# Sensormain_of_Tatebayashi.net
KiCad netlist of a schematic drawn in EAGLE
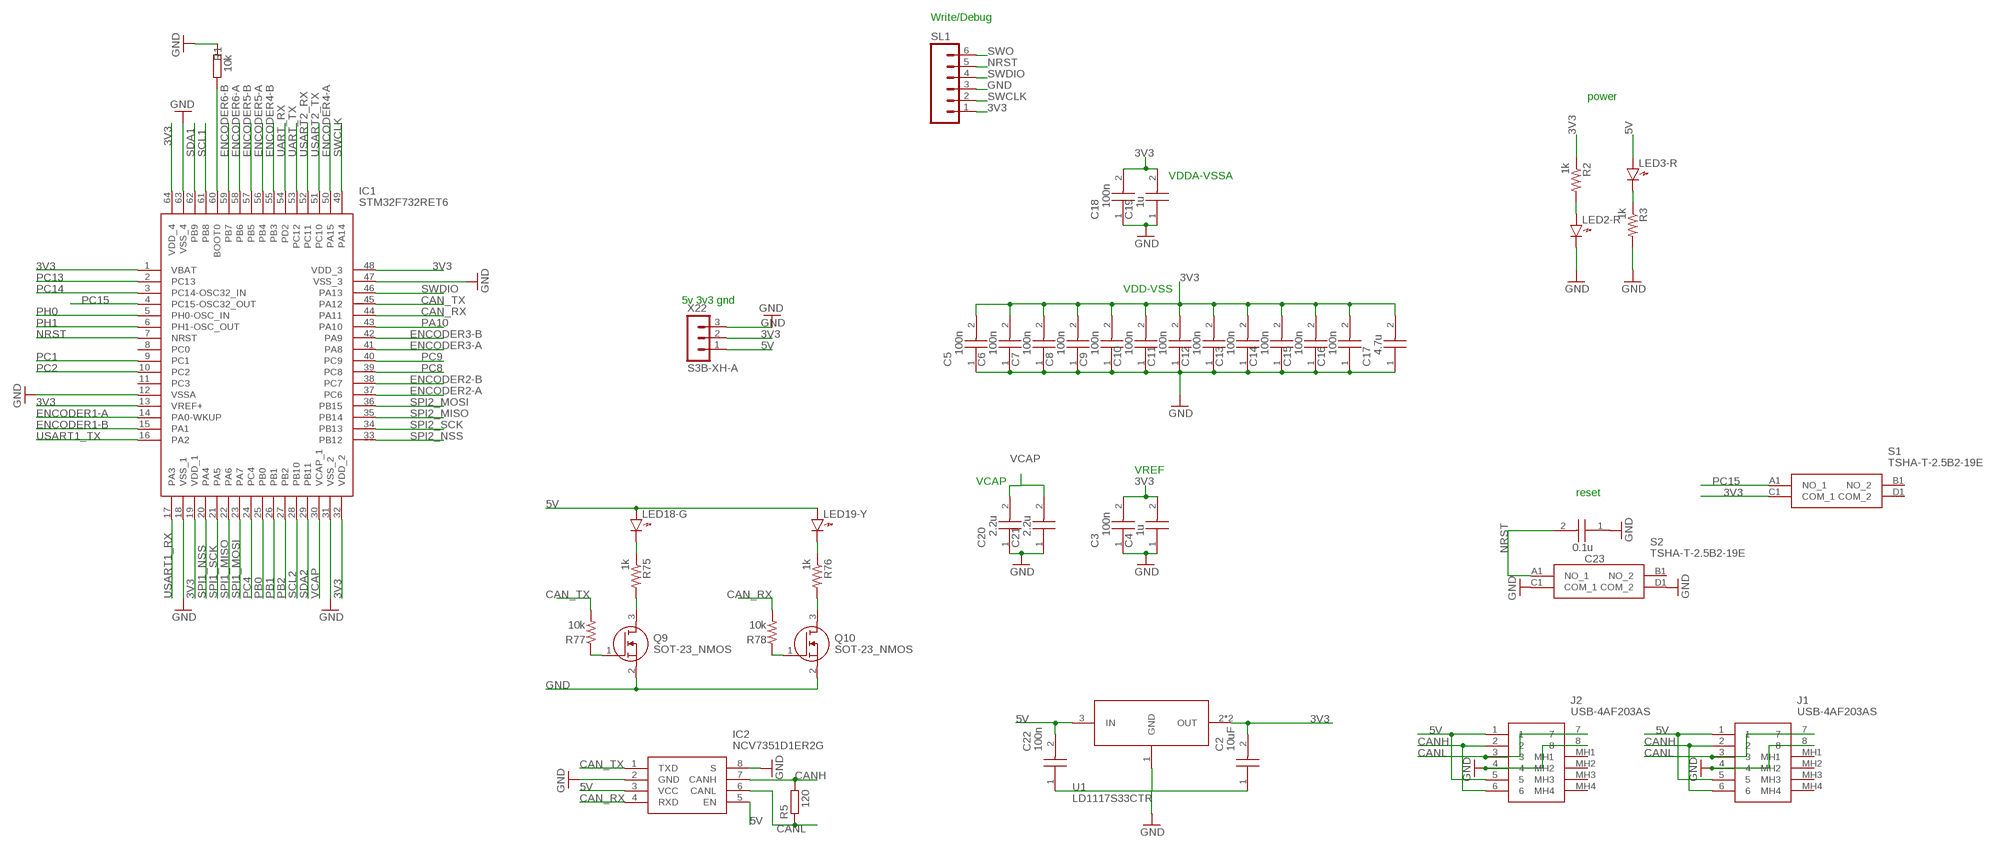
[diagram p0: schematic, sheet 1]
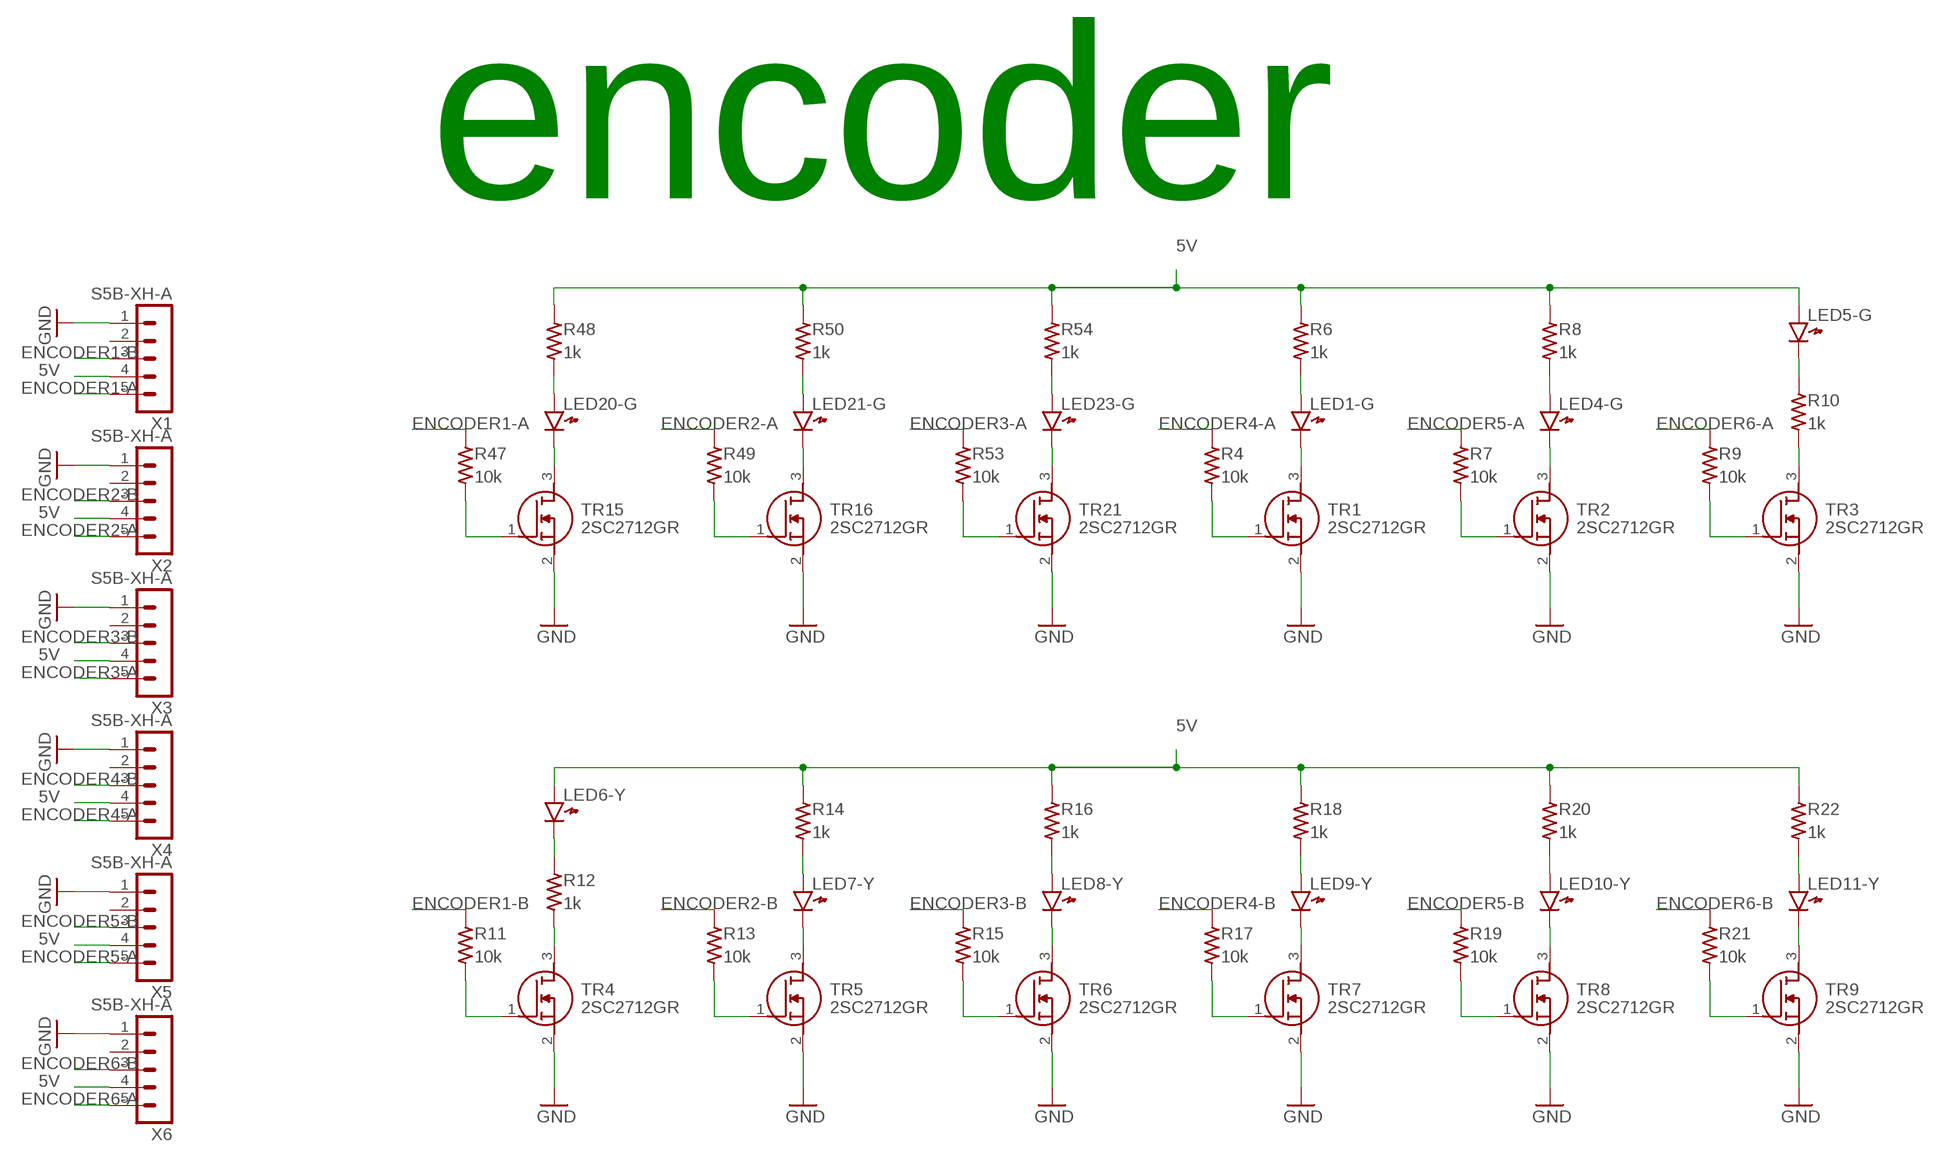
[diagram p1: schematic, sheet 2]
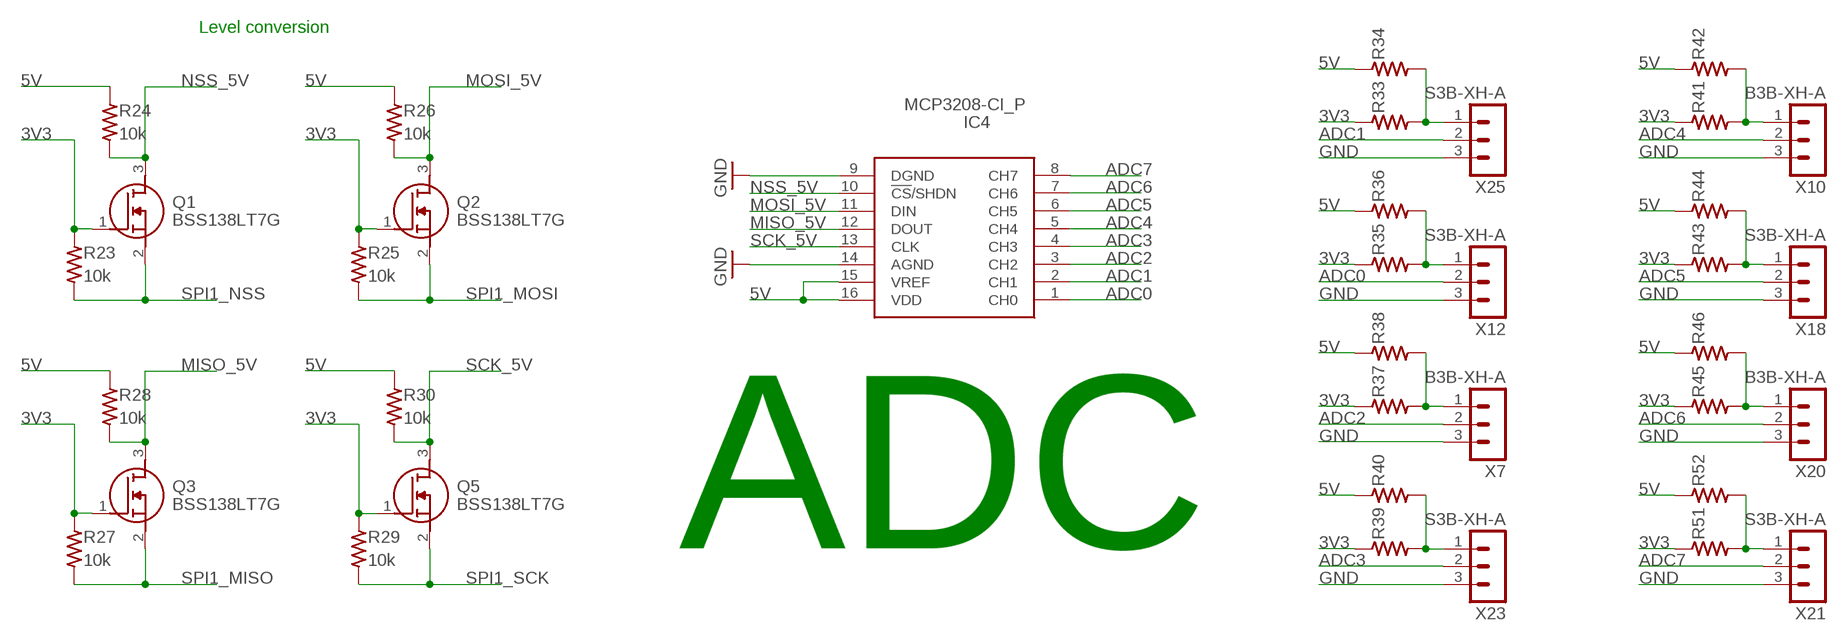
[diagram p2: schematic, sheet 3]
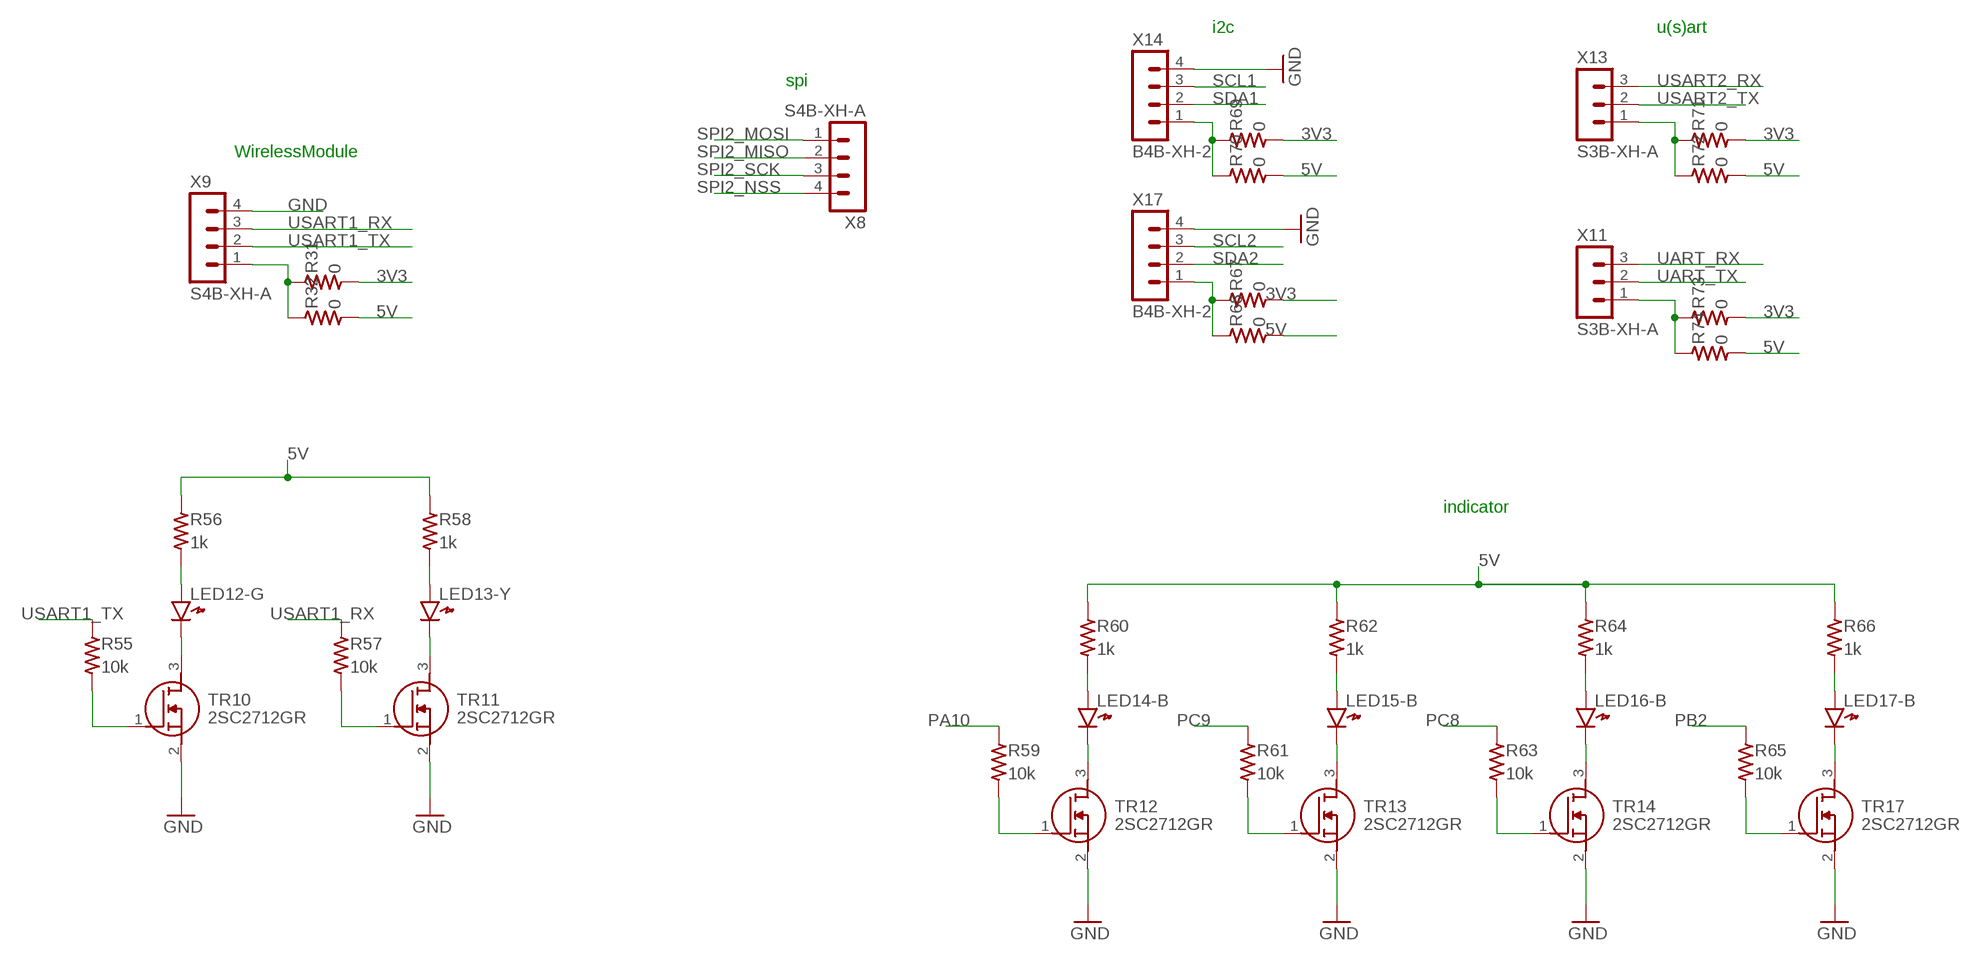
[diagram p3: schematic, sheet 4]
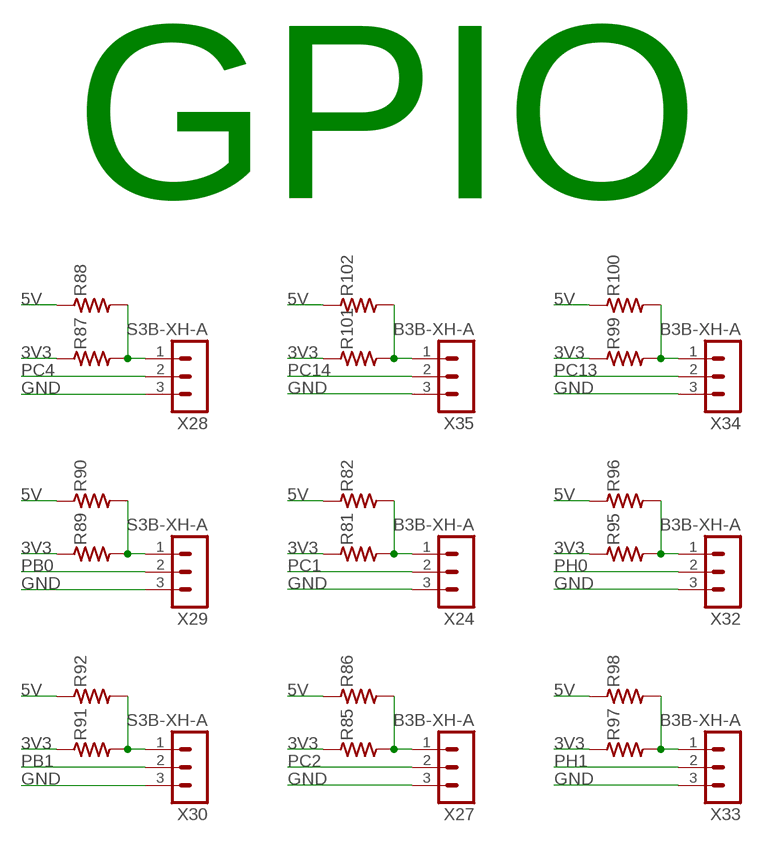
[diagram p4: schematic, sheet 5]

(export (version "E")
  (design (tool "Eeschema 10.0.6"))
  (components
    (comp (ref "C2")
      (value "10uF")
      (footprint "eagle-import:CAPC1608X90N")
      (fields
        (field (name "MANUFACTURER_PART_NUMBER") "GRM188B31A106KE69D")
        (field (name "RS_PART_NUMBER") "8847157P")
      )
      (libsource (lib "eagle-import") (part "GRM188B31A106KE69D"))
    )
    (comp (ref "C3")
      (value "100n")
      (footprint "eagle-import:CAPC1709X100N")
      (fields
        (field (name "MANUFACTURER_PART_NUMBER") "AMK107BBJ476MA-RE")
        (field (name "MOUSER_PART_NUMBER") "963-AMK107BBJ476MARE")
        (field (name "RS_PART_NUMBER") "1843762P")
      )
      (libsource (lib "eagle-import") (part "AMK107BBJ476MA-RE"))
    )
    (comp (ref "C4")
      (value "1u")
      (footprint "eagle-import:CAPC1709X100N")
      (fields
        (field (name "MANUFACTURER_PART_NUMBER") "AMK107BBJ476MA-RE")
        (field (name "MOUSER_PART_NUMBER") "963-AMK107BBJ476MARE")
        (field (name "RS_PART_NUMBER") "1843762P")
      )
      (libsource (lib "eagle-import") (part "AMK107BBJ476MA-RE"))
    )
    (comp (ref "C5")
      (value "100n")
      (footprint "eagle-import:CAPC1709X100N")
      (fields
        (field (name "MANUFACTURER_PART_NUMBER") "AMK107BBJ476MA-RE")
        (field (name "MOUSER_PART_NUMBER") "963-AMK107BBJ476MARE")
        (field (name "RS_PART_NUMBER") "1843762P")
      )
      (libsource (lib "eagle-import") (part "AMK107BBJ476MA-RE"))
    )
    (comp (ref "C6")
      (value "100n")
      (footprint "eagle-import:CAPC1709X100N")
      (fields
        (field (name "MANUFACTURER_PART_NUMBER") "AMK107BBJ476MA-RE")
        (field (name "MOUSER_PART_NUMBER") "963-AMK107BBJ476MARE")
        (field (name "RS_PART_NUMBER") "1843762P")
      )
      (libsource (lib "eagle-import") (part "AMK107BBJ476MA-RE"))
    )
    (comp (ref "C7")
      (value "100n")
      (footprint "eagle-import:CAPC1709X100N")
      (fields
        (field (name "MANUFACTURER_PART_NUMBER") "AMK107BBJ476MA-RE")
        (field (name "MOUSER_PART_NUMBER") "963-AMK107BBJ476MARE")
        (field (name "RS_PART_NUMBER") "1843762P")
      )
      (libsource (lib "eagle-import") (part "AMK107BBJ476MA-RE"))
    )
    (comp (ref "C8")
      (value "100n")
      (footprint "eagle-import:CAPC1709X100N")
      (fields
        (field (name "MANUFACTURER_PART_NUMBER") "AMK107BBJ476MA-RE")
        (field (name "MOUSER_PART_NUMBER") "963-AMK107BBJ476MARE")
        (field (name "RS_PART_NUMBER") "1843762P")
      )
      (libsource (lib "eagle-import") (part "AMK107BBJ476MA-RE"))
    )
    (comp (ref "C9")
      (value "100n")
      (footprint "eagle-import:CAPC1709X100N")
      (fields
        (field (name "MANUFACTURER_PART_NUMBER") "AMK107BBJ476MA-RE")
        (field (name "MOUSER_PART_NUMBER") "963-AMK107BBJ476MARE")
        (field (name "RS_PART_NUMBER") "1843762P")
      )
      (libsource (lib "eagle-import") (part "AMK107BBJ476MA-RE"))
    )
    (comp (ref "C10")
      (value "100n")
      (footprint "eagle-import:CAPC1709X100N")
      (fields
        (field (name "MANUFACTURER_PART_NUMBER") "AMK107BBJ476MA-RE")
        (field (name "MOUSER_PART_NUMBER") "963-AMK107BBJ476MARE")
        (field (name "RS_PART_NUMBER") "1843762P")
      )
      (libsource (lib "eagle-import") (part "AMK107BBJ476MA-RE"))
    )
    (comp (ref "C11")
      (value "100n")
      (footprint "eagle-import:CAPC1709X100N")
      (fields
        (field (name "MANUFACTURER_PART_NUMBER") "AMK107BBJ476MA-RE")
        (field (name "MOUSER_PART_NUMBER") "963-AMK107BBJ476MARE")
        (field (name "RS_PART_NUMBER") "1843762P")
      )
      (libsource (lib "eagle-import") (part "AMK107BBJ476MA-RE"))
    )
    (comp (ref "C12")
      (value "100n")
      (footprint "eagle-import:CAPC1709X100N")
      (fields
        (field (name "MANUFACTURER_PART_NUMBER") "AMK107BBJ476MA-RE")
        (field (name "MOUSER_PART_NUMBER") "963-AMK107BBJ476MARE")
        (field (name "RS_PART_NUMBER") "1843762P")
      )
      (libsource (lib "eagle-import") (part "AMK107BBJ476MA-RE"))
    )
    (comp (ref "C13")
      (value "100n")
      (footprint "eagle-import:CAPC1709X100N")
      (fields
        (field (name "MANUFACTURER_PART_NUMBER") "AMK107BBJ476MA-RE")
        (field (name "MOUSER_PART_NUMBER") "963-AMK107BBJ476MARE")
        (field (name "RS_PART_NUMBER") "1843762P")
      )
      (libsource (lib "eagle-import") (part "AMK107BBJ476MA-RE"))
    )
    (comp (ref "C14")
      (value "100n")
      (footprint "eagle-import:CAPC1709X100N")
      (fields
        (field (name "MANUFACTURER_PART_NUMBER") "AMK107BBJ476MA-RE")
        (field (name "MOUSER_PART_NUMBER") "963-AMK107BBJ476MARE")
        (field (name "RS_PART_NUMBER") "1843762P")
      )
      (libsource (lib "eagle-import") (part "AMK107BBJ476MA-RE"))
    )
    (comp (ref "C15")
      (value "100n")
      (footprint "eagle-import:CAPC1709X100N")
      (fields
        (field (name "MANUFACTURER_PART_NUMBER") "AMK107BBJ476MA-RE")
        (field (name "MOUSER_PART_NUMBER") "963-AMK107BBJ476MARE")
        (field (name "RS_PART_NUMBER") "1843762P")
      )
      (libsource (lib "eagle-import") (part "AMK107BBJ476MA-RE"))
    )
    (comp (ref "C16")
      (value "100n")
      (footprint "eagle-import:CAPC1709X100N")
      (fields
        (field (name "MANUFACTURER_PART_NUMBER") "AMK107BBJ476MA-RE")
        (field (name "MOUSER_PART_NUMBER") "963-AMK107BBJ476MARE")
        (field (name "RS_PART_NUMBER") "1843762P")
      )
      (libsource (lib "eagle-import") (part "AMK107BBJ476MA-RE"))
    )
    (comp (ref "C17")
      (value "4.7u")
      (footprint "eagle-import:CAPC1709X100N")
      (fields
        (field (name "MANUFACTURER_PART_NUMBER") "AMK107BBJ476MA-RE")
        (field (name "MOUSER_PART_NUMBER") "963-AMK107BBJ476MARE")
        (field (name "RS_PART_NUMBER") "1843762P")
      )
      (libsource (lib "eagle-import") (part "AMK107BBJ476MA-RE"))
    )
    (comp (ref "C18")
      (value "100n")
      (footprint "eagle-import:CAPC1709X100N")
      (fields
        (field (name "MANUFACTURER_PART_NUMBER") "AMK107BBJ476MA-RE")
        (field (name "MOUSER_PART_NUMBER") "963-AMK107BBJ476MARE")
        (field (name "RS_PART_NUMBER") "1843762P")
      )
      (libsource (lib "eagle-import") (part "AMK107BBJ476MA-RE"))
    )
    (comp (ref "C19")
      (value "1u")
      (footprint "eagle-import:CAPC1709X100N")
      (fields
        (field (name "MANUFACTURER_PART_NUMBER") "AMK107BBJ476MA-RE")
        (field (name "MOUSER_PART_NUMBER") "963-AMK107BBJ476MARE")
        (field (name "RS_PART_NUMBER") "1843762P")
      )
      (libsource (lib "eagle-import") (part "AMK107BBJ476MA-RE"))
    )
    (comp (ref "C20")
      (value "2.2u")
      (footprint "eagle-import:CAPC1709X100N")
      (fields
        (field (name "MANUFACTURER_PART_NUMBER") "AMK107BBJ476MA-RE")
        (field (name "MOUSER_PART_NUMBER") "963-AMK107BBJ476MARE")
        (field (name "RS_PART_NUMBER") "1843762P")
      )
      (libsource (lib "eagle-import") (part "AMK107BBJ476MA-RE"))
    )
    (comp (ref "C21")
      (value "2.2u")
      (footprint "eagle-import:CAPC1709X100N")
      (fields
        (field (name "MANUFACTURER_PART_NUMBER") "AMK107BBJ476MA-RE")
        (field (name "MOUSER_PART_NUMBER") "963-AMK107BBJ476MARE")
        (field (name "RS_PART_NUMBER") "1843762P")
      )
      (libsource (lib "eagle-import") (part "AMK107BBJ476MA-RE"))
    )
    (comp (ref "C22")
      (value "100n")
      (footprint "eagle-import:CAPC1608X90N")
      (fields
        (field (name "MANUFACTURER_PART_NUMBER") "GRM188B31A106KE69D")
        (field (name "RS_PART_NUMBER") "8847157P")
      )
      (libsource (lib "eagle-import") (part "GRM188B31A106KE69D"))
    )
    (comp (ref "C23")
      (value "0.1u")
      (footprint "eagle-import:CAPC1709X100N")
      (fields
        (field (name "MANUFACTURER_PART_NUMBER") "AMK107BBJ476MA-RE")
        (field (name "MOUSER_PART_NUMBER") "963-AMK107BBJ476MARE")
        (field (name "RS_PART_NUMBER") "1843762P")
      )
      (libsource (lib "eagle-import") (part "AMK107BBJ476MA-RE"))
    )
    (comp (ref "IC1")
      (value "STM32F732RET6")
      (footprint "eagle-import:QFP50P1200X1200X160-64N")
      (fields (field (name "MOUSER_PART_NUMBER") "511-STM32F732RET6"))
      (libsource (lib "eagle-import") (part "STM32F732RET6"))
    )
    (comp (ref "IC2")
      (value "NCV7351D1ER2G")
      (footprint "eagle-import:SOIC127P600X175-8N")
      (fields (field (name "MOUSER_PART_NUMBER") "863-NCV7351D1ER2G"))
      (libsource (lib "eagle-import") (part "NCV7351D1ER2G"))
    )
    (comp (ref "J1")
      (value "USB-4AF203AS")
      (footprint "eagle-import:USB4AF203AS")
      (libsource (lib "eagle-import") (part "USB-4AF203AS"))
    )
    (comp (ref "J2")
      (value "USB-4AF203AS")
      (footprint "eagle-import:USB4AF203AS")
      (libsource (lib "eagle-import") (part "USB-4AF203AS"))
    )
    (comp (ref "LED2-R")
      (value "LED1608")
      (footprint "eagle-import:LED1608")
      (libsource (lib "eagle-import") (part "LED1608"))
    )
    (comp (ref "LED3-R")
      (value "LED1608")
      (footprint "eagle-import:LED1608")
      (libsource (lib "eagle-import") (part "LED1608"))
    )
    (comp (ref "LED18-G")
      (value "LED1608")
      (footprint "eagle-import:LED1608")
      (libsource (lib "eagle-import") (part "LED1608"))
    )
    (comp (ref "LED19-Y")
      (value "LED1608")
      (footprint "eagle-import:LED1608")
      (libsource (lib "eagle-import") (part "LED1608"))
    )
    (comp (ref "Q9")
      (value "SOT-23_NMOS")
      (footprint "eagle-import:SOT-23")
      (libsource (lib "eagle-import") (part "SOT-23_NMOS"))
    )
    (comp (ref "Q10")
      (value "SOT-23_NMOS")
      (footprint "eagle-import:SOT-23")
      (libsource (lib "eagle-import") (part "SOT-23_NMOS"))
    )
    (comp (ref "R1")
      (value "10k")
      (footprint "eagle-import:1608")
      (libsource (lib "eagle-import") (part "R1608"))
    )
    (comp (ref "R2")
      (value "1k")
      (footprint "eagle-import:R0603")
      (libsource (lib "eagle-import") (part "R-US_R0603"))
    )
    (comp (ref "R3")
      (value "1k")
      (footprint "eagle-import:R0603")
      (libsource (lib "eagle-import") (part "R-US_R0603"))
    )
    (comp (ref "R5")
      (value "120")
      (footprint "eagle-import:R0805")
      (libsource (lib "eagle-import") (part "R-EU_R0805"))
    )
    (comp (ref "R75")
      (value "1k")
      (footprint "eagle-import:R0603")
      (libsource (lib "eagle-import") (part "R-US_R0603"))
    )
    (comp (ref "R76")
      (value "1k")
      (footprint "eagle-import:R0603")
      (libsource (lib "eagle-import") (part "R-US_R0603"))
    )
    (comp (ref "R77")
      (value "10k")
      (footprint "eagle-import:SMD1608")
      (libsource (lib "eagle-import") (part "RESISTOR-US1608"))
    )
    (comp (ref "R78")
      (value "10k")
      (footprint "eagle-import:SMD1608")
      (libsource (lib "eagle-import") (part "RESISTOR-US1608"))
    )
    (comp (ref "S1")
      (value "TSHA-T-2.5B2-19E")
      (footprint "eagle-import:TSHAT25B219E")
      (libsource (lib "eagle-import") (part "TSHA-T-2.5B2-19E"))
    )
    (comp (ref "S2")
      (value "TSHA-T-2.5B2-19E")
      (footprint "eagle-import:TSHAT25B219E")
      (libsource (lib "eagle-import") (part "TSHA-T-2.5B2-19E"))
    )
    (comp (ref "SL1")
      (value "MA06")
      (footprint "eagle-import:06PA")
      (libsource (lib "eagle-import") (part "MA06"))
    )
    (comp (ref "U1")
      (value "LD1117S33CTR")
      (footprint "eagle-import:SOT223")
      (fields (field (name "MF") "STMicroelectronics"))
      (libsource (lib "eagle-import") (part "LD1117S33CTR"))
    )
    (comp (ref "X22")
      (value "S3B-XH-A")
      (footprint "eagle-import:S3B-XH-A")
      (libsource (lib "eagle-import") (part "con-JST_XH_S3B-XH-A"))
    )
    (comp (ref "LED12-G")
      (value "LED1608")
      (footprint "eagle-import:LED1608")
      (libsource (lib "eagle-import") (part "LED1608"))
    )
    (comp (ref "LED13-Y")
      (value "LED1608")
      (footprint "eagle-import:LED1608")
      (libsource (lib "eagle-import") (part "LED1608"))
    )
    (comp (ref "LED14-B")
      (value "LED1608")
      (footprint "eagle-import:LED1608")
      (libsource (lib "eagle-import") (part "LED1608"))
    )
    (comp (ref "LED15-B")
      (value "LED1608")
      (footprint "eagle-import:LED1608")
      (libsource (lib "eagle-import") (part "LED1608"))
    )
    (comp (ref "LED16-B")
      (value "LED1608")
      (footprint "eagle-import:LED1608")
      (libsource (lib "eagle-import") (part "LED1608"))
    )
    (comp (ref "LED17-B")
      (value "LED1608")
      (footprint "eagle-import:LED1608")
      (libsource (lib "eagle-import") (part "LED1608"))
    )
    (comp (ref "R31")
      (value "0")
      (footprint "eagle-import:SMD1608")
      (libsource (lib "eagle-import") (part "RESISTOR-US1608"))
    )
    (comp (ref "R32")
      (value "0")
      (footprint "eagle-import:SMD1608")
      (libsource (lib "eagle-import") (part "RESISTOR-US1608"))
    )
    (comp (ref "R55")
      (value "10k")
      (footprint "eagle-import:SMD1608")
      (libsource (lib "eagle-import") (part "RESISTOR-US1608"))
    )
    (comp (ref "R56")
      (value "1k")
      (footprint "eagle-import:SMD1608")
      (libsource (lib "eagle-import") (part "RESISTOR-US1608"))
    )
    (comp (ref "R57")
      (value "10k")
      (footprint "eagle-import:SMD1608")
      (libsource (lib "eagle-import") (part "RESISTOR-US1608"))
    )
    (comp (ref "R58")
      (value "1k")
      (footprint "eagle-import:SMD1608")
      (libsource (lib "eagle-import") (part "RESISTOR-US1608"))
    )
    (comp (ref "R59")
      (value "10k")
      (footprint "eagle-import:SMD1608")
      (libsource (lib "eagle-import") (part "RESISTOR-US1608"))
    )
    (comp (ref "R60")
      (value "1k")
      (footprint "eagle-import:SMD1608")
      (libsource (lib "eagle-import") (part "RESISTOR-US1608"))
    )
    (comp (ref "R61")
      (value "10k")
      (footprint "eagle-import:SMD1608")
      (libsource (lib "eagle-import") (part "RESISTOR-US1608"))
    )
    (comp (ref "R62")
      (value "1k")
      (footprint "eagle-import:SMD1608")
      (libsource (lib "eagle-import") (part "RESISTOR-US1608"))
    )
    (comp (ref "R63")
      (value "10k")
      (footprint "eagle-import:SMD1608")
      (libsource (lib "eagle-import") (part "RESISTOR-US1608"))
    )
    (comp (ref "R64")
      (value "1k")
      (footprint "eagle-import:SMD1608")
      (libsource (lib "eagle-import") (part "RESISTOR-US1608"))
    )
    (comp (ref "R65")
      (value "10k")
      (footprint "eagle-import:SMD1608")
      (libsource (lib "eagle-import") (part "RESISTOR-US1608"))
    )
    (comp (ref "R66")
      (value "1k")
      (footprint "eagle-import:SMD1608")
      (libsource (lib "eagle-import") (part "RESISTOR-US1608"))
    )
    (comp (ref "R67")
      (value "0")
      (footprint "eagle-import:SMD1608")
      (libsource (lib "eagle-import") (part "RESISTOR-US1608"))
    )
    (comp (ref "R68")
      (value "0")
      (footprint "eagle-import:SMD1608")
      (libsource (lib "eagle-import") (part "RESISTOR-US1608"))
    )
    (comp (ref "R69")
      (value "0")
      (footprint "eagle-import:SMD1608")
      (libsource (lib "eagle-import") (part "RESISTOR-US1608"))
    )
    (comp (ref "R70")
      (value "0")
      (footprint "eagle-import:SMD1608")
      (libsource (lib "eagle-import") (part "RESISTOR-US1608"))
    )
    (comp (ref "R71")
      (value "0")
      (footprint "eagle-import:SMD1608")
      (libsource (lib "eagle-import") (part "RESISTOR-US1608"))
    )
    (comp (ref "R72")
      (value "0")
      (footprint "eagle-import:SMD1608")
      (libsource (lib "eagle-import") (part "RESISTOR-US1608"))
    )
    (comp (ref "R73")
      (value "0")
      (footprint "eagle-import:SMD1608")
      (libsource (lib "eagle-import") (part "RESISTOR-US1608"))
    )
    (comp (ref "R74")
      (value "0")
      (footprint "eagle-import:SMD1608")
      (libsource (lib "eagle-import") (part "RESISTOR-US1608"))
    )
    (comp (ref "TR10")
      (value "2SC2712GR")
      (footprint "eagle-import:SOT-23")
      (libsource (lib "eagle-import") (part "SOT-23_NMOS"))
    )
    (comp (ref "TR11")
      (value "2SC2712GR")
      (footprint "eagle-import:SOT-23")
      (libsource (lib "eagle-import") (part "SOT-23_NMOS"))
    )
    (comp (ref "TR12")
      (value "2SC2712GR")
      (footprint "eagle-import:SOT-23")
      (libsource (lib "eagle-import") (part "SOT-23_NMOS"))
    )
    (comp (ref "TR13")
      (value "2SC2712GR")
      (footprint "eagle-import:SOT-23")
      (libsource (lib "eagle-import") (part "SOT-23_NMOS"))
    )
    (comp (ref "TR14")
      (value "2SC2712GR")
      (footprint "eagle-import:SOT-23")
      (libsource (lib "eagle-import") (part "SOT-23_NMOS"))
    )
    (comp (ref "TR17")
      (value "2SC2712GR")
      (footprint "eagle-import:SOT-23")
      (libsource (lib "eagle-import") (part "SOT-23_NMOS"))
    )
    (comp (ref "X8")
      (value "S4B-XH-A")
      (footprint "eagle-import:S4B-XH-A")
      (libsource (lib "eagle-import") (part "S4B-XH-A"))
    )
    (comp (ref "X9")
      (value "S4B-XH-A")
      (footprint "eagle-import:S4B-XH-A")
      (libsource (lib "eagle-import") (part "S4B-XH-A"))
    )
    (comp (ref "X11")
      (value "S3B-XH-A")
      (footprint "eagle-import:S3B-XH-A")
      (libsource (lib "eagle-import") (part "S3B-XH-A"))
    )
    (comp (ref "X13")
      (value "S3B-XH-A")
      (footprint "eagle-import:S3B-XH-A")
      (libsource (lib "eagle-import") (part "S3B-XH-A"))
    )
    (comp (ref "X14")
      (value "B4B-XH-2")
      (footprint "eagle-import:B4B-XH-A")
      (libsource (lib "eagle-import") (part "B4B-XH-2"))
    )
    (comp (ref "X17")
      (value "B4B-XH-2")
      (footprint "eagle-import:B4B-XH-A")
      (libsource (lib "eagle-import") (part "B4B-XH-2"))
    )
    (comp (ref "R81")
      (value "RESISTOR-US1608")
      (footprint "eagle-import:SMD1608")
      (libsource (lib "eagle-import") (part "RESISTOR-US1608"))
    )
    (comp (ref "R82")
      (value "RESISTOR-US1608")
      (footprint "eagle-import:SMD1608")
      (libsource (lib "eagle-import") (part "RESISTOR-US1608"))
    )
    (comp (ref "R85")
      (value "RESISTOR-US1608")
      (footprint "eagle-import:SMD1608")
      (libsource (lib "eagle-import") (part "RESISTOR-US1608"))
    )
    (comp (ref "R86")
      (value "RESISTOR-US1608")
      (footprint "eagle-import:SMD1608")
      (libsource (lib "eagle-import") (part "RESISTOR-US1608"))
    )
    (comp (ref "R87")
      (value "RESISTOR-US1608")
      (footprint "eagle-import:SMD1608")
      (libsource (lib "eagle-import") (part "RESISTOR-US1608"))
    )
    (comp (ref "R88")
      (value "RESISTOR-US1608")
      (footprint "eagle-import:SMD1608")
      (libsource (lib "eagle-import") (part "RESISTOR-US1608"))
    )
    (comp (ref "R89")
      (value "RESISTOR-US1608")
      (footprint "eagle-import:SMD1608")
      (libsource (lib "eagle-import") (part "RESISTOR-US1608"))
    )
    (comp (ref "R90")
      (value "RESISTOR-US1608")
      (footprint "eagle-import:SMD1608")
      (libsource (lib "eagle-import") (part "RESISTOR-US1608"))
    )
    (comp (ref "R91")
      (value "RESISTOR-US1608")
      (footprint "eagle-import:SMD1608")
      (libsource (lib "eagle-import") (part "RESISTOR-US1608"))
    )
    (comp (ref "R92")
      (value "RESISTOR-US1608")
      (footprint "eagle-import:SMD1608")
      (libsource (lib "eagle-import") (part "RESISTOR-US1608"))
    )
    (comp (ref "R95")
      (value "RESISTOR-US1608")
      (footprint "eagle-import:SMD1608")
      (libsource (lib "eagle-import") (part "RESISTOR-US1608"))
    )
    (comp (ref "R96")
      (value "RESISTOR-US1608")
      (footprint "eagle-import:SMD1608")
      (libsource (lib "eagle-import") (part "RESISTOR-US1608"))
    )
    (comp (ref "R97")
      (value "RESISTOR-US1608")
      (footprint "eagle-import:SMD1608")
      (libsource (lib "eagle-import") (part "RESISTOR-US1608"))
    )
    (comp (ref "R98")
      (value "RESISTOR-US1608")
      (footprint "eagle-import:SMD1608")
      (libsource (lib "eagle-import") (part "RESISTOR-US1608"))
    )
    (comp (ref "R99")
      (value "RESISTOR-US1608")
      (footprint "eagle-import:SMD1608")
      (libsource (lib "eagle-import") (part "RESISTOR-US1608"))
    )
    (comp (ref "R100")
      (value "RESISTOR-US1608")
      (footprint "eagle-import:SMD1608")
      (libsource (lib "eagle-import") (part "RESISTOR-US1608"))
    )
    (comp (ref "R101")
      (value "RESISTOR-US1608")
      (footprint "eagle-import:SMD1608")
      (libsource (lib "eagle-import") (part "RESISTOR-US1608"))
    )
    (comp (ref "R102")
      (value "RESISTOR-US1608")
      (footprint "eagle-import:SMD1608")
      (libsource (lib "eagle-import") (part "RESISTOR-US1608"))
    )
    (comp (ref "X24")
      (value "B3B-XH-A")
      (footprint "eagle-import:B3B-XH-A")
      (libsource (lib "eagle-import") (part "B3B-XH-A"))
    )
    (comp (ref "X27")
      (value "B3B-XH-A")
      (footprint "eagle-import:B3B-XH-A")
      (libsource (lib "eagle-import") (part "B3B-XH-A"))
    )
    (comp (ref "X28")
      (value "S3B-XH-A")
      (footprint "eagle-import:S3B-XH-A")
      (libsource (lib "eagle-import") (part "S3B-XH-A"))
    )
    (comp (ref "X29")
      (value "S3B-XH-A")
      (footprint "eagle-import:S3B-XH-A")
      (libsource (lib "eagle-import") (part "S3B-XH-A"))
    )
    (comp (ref "X30")
      (value "S3B-XH-A")
      (footprint "eagle-import:S3B-XH-A")
      (libsource (lib "eagle-import") (part "S3B-XH-A"))
    )
    (comp (ref "X32")
      (value "B3B-XH-A")
      (footprint "eagle-import:B3B-XH-A")
      (libsource (lib "eagle-import") (part "B3B-XH-A"))
    )
    (comp (ref "X33")
      (value "B3B-XH-A")
      (footprint "eagle-import:B3B-XH-A")
      (libsource (lib "eagle-import") (part "B3B-XH-A"))
    )
    (comp (ref "X34")
      (value "B3B-XH-A")
      (footprint "eagle-import:B3B-XH-A")
      (libsource (lib "eagle-import") (part "B3B-XH-A"))
    )
    (comp (ref "X35")
      (value "B3B-XH-A")
      (footprint "eagle-import:B3B-XH-A")
      (libsource (lib "eagle-import") (part "B3B-XH-A"))
    )
    (comp (ref "IC4")
      (value "MCP3208-CI_P")
      (footprint "eagle-import:DIP781W56P254L1918H533Q16N")
      (fields
        (field (name "ARROW_PART_NUMBER") "MCP3208-CI/P")
        (field (name "MOUSER_PART_NUMBER") "579-MCP3208CIP")
      )
      (libsource (lib "eagle-import") (part "MCP3208-CI_P"))
    )
    (comp (ref "Q1")
      (value "BSS138LT7G")
      (footprint "eagle-import:SOT96P237X111-3N")
      (fields (field (name "MOUSER_PART_NUMBER") "863-BSS138LT7G"))
      (libsource (lib "eagle-import") (part "BSS138LT7G"))
    )
    (comp (ref "Q2")
      (value "BSS138LT7G")
      (footprint "eagle-import:SOT96P237X111-3N")
      (fields (field (name "MOUSER_PART_NUMBER") "863-BSS138LT7G"))
      (libsource (lib "eagle-import") (part "BSS138LT7G"))
    )
    (comp (ref "Q3")
      (value "BSS138LT7G")
      (footprint "eagle-import:SOT96P237X111-3N")
      (fields (field (name "MOUSER_PART_NUMBER") "863-BSS138LT7G"))
      (libsource (lib "eagle-import") (part "BSS138LT7G"))
    )
    (comp (ref "Q5")
      (value "BSS138LT7G")
      (footprint "eagle-import:SOT96P237X111-3N")
      (fields (field (name "MOUSER_PART_NUMBER") "863-BSS138LT7G"))
      (libsource (lib "eagle-import") (part "BSS138LT7G"))
    )
    (comp (ref "R23")
      (value "10k")
      (footprint "eagle-import:SMD1608")
      (libsource (lib "eagle-import") (part "RESISTOR-US1608"))
    )
    (comp (ref "R24")
      (value "10k")
      (footprint "eagle-import:SMD1608")
      (libsource (lib "eagle-import") (part "RESISTOR-US1608"))
    )
    (comp (ref "R25")
      (value "10k")
      (footprint "eagle-import:SMD1608")
      (libsource (lib "eagle-import") (part "RESISTOR-US1608"))
    )
    (comp (ref "R26")
      (value "10k")
      (footprint "eagle-import:SMD1608")
      (libsource (lib "eagle-import") (part "RESISTOR-US1608"))
    )
    (comp (ref "R27")
      (value "10k")
      (footprint "eagle-import:SMD1608")
      (libsource (lib "eagle-import") (part "RESISTOR-US1608"))
    )
    (comp (ref "R28")
      (value "10k")
      (footprint "eagle-import:SMD1608")
      (libsource (lib "eagle-import") (part "RESISTOR-US1608"))
    )
    (comp (ref "R29")
      (value "10k")
      (footprint "eagle-import:SMD1608")
      (libsource (lib "eagle-import") (part "RESISTOR-US1608"))
    )
    (comp (ref "R30")
      (value "10k")
      (footprint "eagle-import:SMD1608")
      (libsource (lib "eagle-import") (part "RESISTOR-US1608"))
    )
    (comp (ref "R33")
      (value "RESISTOR-US1608")
      (footprint "eagle-import:SMD1608")
      (libsource (lib "eagle-import") (part "RESISTOR-US1608"))
    )
    (comp (ref "R34")
      (value "RESISTOR-US1608")
      (footprint "eagle-import:SMD1608")
      (libsource (lib "eagle-import") (part "RESISTOR-US1608"))
    )
    (comp (ref "R35")
      (value "RESISTOR-US1608")
      (footprint "eagle-import:SMD1608")
      (libsource (lib "eagle-import") (part "RESISTOR-US1608"))
    )
    (comp (ref "R36")
      (value "RESISTOR-US1608")
      (footprint "eagle-import:SMD1608")
      (libsource (lib "eagle-import") (part "RESISTOR-US1608"))
    )
    (comp (ref "R37")
      (value "RESISTOR-US1608")
      (footprint "eagle-import:SMD1608")
      (libsource (lib "eagle-import") (part "RESISTOR-US1608"))
    )
    (comp (ref "R38")
      (value "RESISTOR-US1608")
      (footprint "eagle-import:SMD1608")
      (libsource (lib "eagle-import") (part "RESISTOR-US1608"))
    )
    (comp (ref "R39")
      (value "RESISTOR-US1608")
      (footprint "eagle-import:SMD1608")
      (libsource (lib "eagle-import") (part "RESISTOR-US1608"))
    )
    (comp (ref "R40")
      (value "RESISTOR-US1608")
      (footprint "eagle-import:SMD1608")
      (libsource (lib "eagle-import") (part "RESISTOR-US1608"))
    )
    (comp (ref "R41")
      (value "RESISTOR-US1608")
      (footprint "eagle-import:SMD1608")
      (libsource (lib "eagle-import") (part "RESISTOR-US1608"))
    )
    (comp (ref "R42")
      (value "RESISTOR-US1608")
      (footprint "eagle-import:SMD1608")
      (libsource (lib "eagle-import") (part "RESISTOR-US1608"))
    )
    (comp (ref "R43")
      (value "RESISTOR-US1608")
      (footprint "eagle-import:SMD1608")
      (libsource (lib "eagle-import") (part "RESISTOR-US1608"))
    )
    (comp (ref "R44")
      (value "RESISTOR-US1608")
      (footprint "eagle-import:SMD1608")
      (libsource (lib "eagle-import") (part "RESISTOR-US1608"))
    )
    (comp (ref "R45")
      (value "RESISTOR-US1608")
      (footprint "eagle-import:SMD1608")
      (libsource (lib "eagle-import") (part "RESISTOR-US1608"))
    )
    (comp (ref "R46")
      (value "RESISTOR-US1608")
      (footprint "eagle-import:SMD1608")
      (libsource (lib "eagle-import") (part "RESISTOR-US1608"))
    )
    (comp (ref "R51")
      (value "RESISTOR-US1608")
      (footprint "eagle-import:SMD1608")
      (libsource (lib "eagle-import") (part "RESISTOR-US1608"))
    )
    (comp (ref "R52")
      (value "RESISTOR-US1608")
      (footprint "eagle-import:SMD1608")
      (libsource (lib "eagle-import") (part "RESISTOR-US1608"))
    )
    (comp (ref "X7")
      (value "B3B-XH-A")
      (footprint "eagle-import:B3B-XH-A")
      (libsource (lib "eagle-import") (part "B3B-XH-A"))
    )
    (comp (ref "X10")
      (value "B3B-XH-A")
      (footprint "eagle-import:B3B-XH-A")
      (libsource (lib "eagle-import") (part "B3B-XH-A"))
    )
    (comp (ref "X12")
      (value "S3B-XH-A")
      (footprint "eagle-import:S3B-XH-A")
      (libsource (lib "eagle-import") (part "S3B-XH-A"))
    )
    (comp (ref "X18")
      (value "S3B-XH-A")
      (footprint "eagle-import:S3B-XH-A")
      (libsource (lib "eagle-import") (part "S3B-XH-A"))
    )
    (comp (ref "X20")
      (value "B3B-XH-A")
      (footprint "eagle-import:B3B-XH-A")
      (libsource (lib "eagle-import") (part "B3B-XH-A"))
    )
    (comp (ref "X21")
      (value "S3B-XH-A")
      (footprint "eagle-import:S3B-XH-A")
      (libsource (lib "eagle-import") (part "S3B-XH-A"))
    )
    (comp (ref "X23")
      (value "S3B-XH-A")
      (footprint "eagle-import:S3B-XH-A")
      (libsource (lib "eagle-import") (part "S3B-XH-A"))
    )
    (comp (ref "X25")
      (value "S3B-XH-A")
      (footprint "eagle-import:S3B-XH-A")
      (libsource (lib "eagle-import") (part "S3B-XH-A"))
    )
    (comp (ref "LED1-G")
      (value "LED1608")
      (footprint "eagle-import:LED1608")
      (libsource (lib "eagle-import") (part "LED1608"))
    )
    (comp (ref "LED4-G")
      (value "LED1608")
      (footprint "eagle-import:LED1608")
      (libsource (lib "eagle-import") (part "LED1608"))
    )
    (comp (ref "LED5-G")
      (value "LED1608")
      (footprint "eagle-import:LED1608")
      (libsource (lib "eagle-import") (part "LED1608"))
    )
    (comp (ref "LED6-Y")
      (value "LED1608")
      (footprint "eagle-import:LED1608")
      (libsource (lib "eagle-import") (part "LED1608"))
    )
    (comp (ref "LED7-Y")
      (value "LED1608")
      (footprint "eagle-import:LED1608")
      (libsource (lib "eagle-import") (part "LED1608"))
    )
    (comp (ref "LED8-Y")
      (value "LED1608")
      (footprint "eagle-import:LED1608")
      (libsource (lib "eagle-import") (part "LED1608"))
    )
    (comp (ref "LED9-Y")
      (value "LED1608")
      (footprint "eagle-import:LED1608")
      (libsource (lib "eagle-import") (part "LED1608"))
    )
    (comp (ref "LED10-Y")
      (value "LED1608")
      (footprint "eagle-import:LED1608")
      (libsource (lib "eagle-import") (part "LED1608"))
    )
    (comp (ref "LED11-Y")
      (value "LED1608")
      (footprint "eagle-import:LED1608")
      (libsource (lib "eagle-import") (part "LED1608"))
    )
    (comp (ref "LED20-G")
      (value "LED1608")
      (footprint "eagle-import:LED1608")
      (libsource (lib "eagle-import") (part "LED1608"))
    )
    (comp (ref "LED21-G")
      (value "LED1608")
      (footprint "eagle-import:LED1608")
      (libsource (lib "eagle-import") (part "LED1608"))
    )
    (comp (ref "LED23-G")
      (value "LED1608")
      (footprint "eagle-import:LED1608")
      (libsource (lib "eagle-import") (part "LED1608"))
    )
    (comp (ref "R4")
      (value "10k")
      (footprint "eagle-import:SMD1608")
      (libsource (lib "eagle-import") (part "RESISTOR-US1608"))
    )
    (comp (ref "R6")
      (value "1k")
      (footprint "eagle-import:SMD1608")
      (libsource (lib "eagle-import") (part "RESISTOR-US1608"))
    )
    (comp (ref "R7")
      (value "10k")
      (footprint "eagle-import:SMD1608")
      (libsource (lib "eagle-import") (part "RESISTOR-US1608"))
    )
    (comp (ref "R8")
      (value "1k")
      (footprint "eagle-import:SMD1608")
      (libsource (lib "eagle-import") (part "RESISTOR-US1608"))
    )
    (comp (ref "R9")
      (value "10k")
      (footprint "eagle-import:SMD1608")
      (libsource (lib "eagle-import") (part "RESISTOR-US1608"))
    )
    (comp (ref "R10")
      (value "1k")
      (footprint "eagle-import:SMD1608")
      (libsource (lib "eagle-import") (part "RESISTOR-US1608"))
    )
    (comp (ref "R11")
      (value "10k")
      (footprint "eagle-import:SMD1608")
      (libsource (lib "eagle-import") (part "RESISTOR-US1608"))
    )
    (comp (ref "R12")
      (value "1k")
      (footprint "eagle-import:SMD1608")
      (libsource (lib "eagle-import") (part "RESISTOR-US1608"))
    )
    (comp (ref "R13")
      (value "10k")
      (footprint "eagle-import:SMD1608")
      (libsource (lib "eagle-import") (part "RESISTOR-US1608"))
    )
    (comp (ref "R14")
      (value "1k")
      (footprint "eagle-import:SMD1608")
      (libsource (lib "eagle-import") (part "RESISTOR-US1608"))
    )
    (comp (ref "R15")
      (value "10k")
      (footprint "eagle-import:SMD1608")
      (libsource (lib "eagle-import") (part "RESISTOR-US1608"))
    )
    (comp (ref "R16")
      (value "1k")
      (footprint "eagle-import:SMD1608")
      (libsource (lib "eagle-import") (part "RESISTOR-US1608"))
    )
    (comp (ref "R17")
      (value "10k")
      (footprint "eagle-import:SMD1608")
      (libsource (lib "eagle-import") (part "RESISTOR-US1608"))
    )
    (comp (ref "R18")
      (value "1k")
      (footprint "eagle-import:SMD1608")
      (libsource (lib "eagle-import") (part "RESISTOR-US1608"))
    )
    (comp (ref "R19")
      (value "10k")
      (footprint "eagle-import:SMD1608")
      (libsource (lib "eagle-import") (part "RESISTOR-US1608"))
    )
    (comp (ref "R20")
      (value "1k")
      (footprint "eagle-import:SMD1608")
      (libsource (lib "eagle-import") (part "RESISTOR-US1608"))
    )
    (comp (ref "R21")
      (value "10k")
      (footprint "eagle-import:SMD1608")
      (libsource (lib "eagle-import") (part "RESISTOR-US1608"))
    )
    (comp (ref "R22")
      (value "1k")
      (footprint "eagle-import:SMD1608")
      (libsource (lib "eagle-import") (part "RESISTOR-US1608"))
    )
    (comp (ref "R47")
      (value "10k")
      (footprint "eagle-import:SMD1608")
      (libsource (lib "eagle-import") (part "RESISTOR-US1608"))
    )
    (comp (ref "R48")
      (value "1k")
      (footprint "eagle-import:SMD1608")
      (libsource (lib "eagle-import") (part "RESISTOR-US1608"))
    )
    (comp (ref "R49")
      (value "10k")
      (footprint "eagle-import:SMD1608")
      (libsource (lib "eagle-import") (part "RESISTOR-US1608"))
    )
    (comp (ref "R50")
      (value "1k")
      (footprint "eagle-import:SMD1608")
      (libsource (lib "eagle-import") (part "RESISTOR-US1608"))
    )
    (comp (ref "R53")
      (value "10k")
      (footprint "eagle-import:SMD1608")
      (libsource (lib "eagle-import") (part "RESISTOR-US1608"))
    )
    (comp (ref "R54")
      (value "1k")
      (footprint "eagle-import:SMD1608")
      (libsource (lib "eagle-import") (part "RESISTOR-US1608"))
    )
    (comp (ref "TR1")
      (value "2SC2712GR")
      (footprint "eagle-import:SOT-23")
      (libsource (lib "eagle-import") (part "SOT-23_NMOS"))
    )
    (comp (ref "TR2")
      (value "2SC2712GR")
      (footprint "eagle-import:SOT-23")
      (libsource (lib "eagle-import") (part "SOT-23_NMOS"))
    )
    (comp (ref "TR3")
      (value "2SC2712GR")
      (footprint "eagle-import:SOT-23")
      (libsource (lib "eagle-import") (part "SOT-23_NMOS"))
    )
    (comp (ref "TR4")
      (value "2SC2712GR")
      (footprint "eagle-import:SOT-23")
      (libsource (lib "eagle-import") (part "SOT-23_NMOS"))
    )
    (comp (ref "TR5")
      (value "2SC2712GR")
      (footprint "eagle-import:SOT-23")
      (libsource (lib "eagle-import") (part "SOT-23_NMOS"))
    )
    (comp (ref "TR6")
      (value "2SC2712GR")
      (footprint "eagle-import:SOT-23")
      (libsource (lib "eagle-import") (part "SOT-23_NMOS"))
    )
    (comp (ref "TR7")
      (value "2SC2712GR")
      (footprint "eagle-import:SOT-23")
      (libsource (lib "eagle-import") (part "SOT-23_NMOS"))
    )
    (comp (ref "TR8")
      (value "2SC2712GR")
      (footprint "eagle-import:SOT-23")
      (libsource (lib "eagle-import") (part "SOT-23_NMOS"))
    )
    (comp (ref "TR9")
      (value "2SC2712GR")
      (footprint "eagle-import:SOT-23")
      (libsource (lib "eagle-import") (part "SOT-23_NMOS"))
    )
    (comp (ref "TR15")
      (value "2SC2712GR")
      (footprint "eagle-import:SOT-23")
      (libsource (lib "eagle-import") (part "SOT-23_NMOS"))
    )
    (comp (ref "TR16")
      (value "2SC2712GR")
      (footprint "eagle-import:SOT-23")
      (libsource (lib "eagle-import") (part "SOT-23_NMOS"))
    )
    (comp (ref "TR21")
      (value "2SC2712GR")
      (footprint "eagle-import:SOT-23")
      (libsource (lib "eagle-import") (part "SOT-23_NMOS"))
    )
    (comp (ref "X1")
      (value "S5B-XH-A")
      (footprint "eagle-import:S5B-XH-A")
      (libsource (lib "eagle-import") (part "S5B-XH-A"))
    )
    (comp (ref "X2")
      (value "S5B-XH-A")
      (footprint "eagle-import:S5B-XH-A")
      (libsource (lib "eagle-import") (part "S5B-XH-A"))
    )
    (comp (ref "X3")
      (value "S5B-XH-A")
      (footprint "eagle-import:S5B-XH-A")
      (libsource (lib "eagle-import") (part "S5B-XH-A"))
    )
    (comp (ref "X4")
      (value "S5B-XH-A")
      (footprint "eagle-import:S5B-XH-A")
      (libsource (lib "eagle-import") (part "S5B-XH-A"))
    )
    (comp (ref "X5")
      (value "S5B-XH-A")
      (footprint "eagle-import:S5B-XH-A")
      (libsource (lib "eagle-import") (part "S5B-XH-A"))
    )
    (comp (ref "X6")
      (value "S5B-XH-A")
      (footprint "eagle-import:S5B-XH-A")
      (libsource (lib "eagle-import") (part "S5B-XH-A"))
    )
  )
  (nets
    (net (code "1") (name "3V3") (class "Default")
      (node (ref "C10") (pin "2") (pinfunction "2_2") (pintype "bidirectional"))
      (node (ref "C11") (pin "2") (pinfunction "2_2") (pintype "bidirectional"))
      (node (ref "C12") (pin "2") (pinfunction "2_2") (pintype "bidirectional"))
      (node (ref "C13") (pin "2") (pinfunction "2_2") (pintype "bidirectional"))
      (node (ref "C14") (pin "2") (pinfunction "2_2") (pintype "bidirectional"))
      (node (ref "C15") (pin "2") (pinfunction "2_2") (pintype "bidirectional"))
      (node (ref "C16") (pin "2") (pinfunction "2_2") (pintype "bidirectional"))
      (node (ref "C17") (pin "2") (pinfunction "2_2") (pintype "bidirectional"))
      (node (ref "C18") (pin "2") (pinfunction "2_2") (pintype "bidirectional"))
      (node (ref "C19") (pin "2") (pinfunction "2_2") (pintype "bidirectional"))
      (node (ref "C2") (pin "2") (pinfunction "2_2") (pintype "bidirectional"))
      (node (ref "C3") (pin "2") (pinfunction "2_2") (pintype "bidirectional"))
      (node (ref "C4") (pin "2") (pinfunction "2_2") (pintype "bidirectional"))
      (node (ref "C5") (pin "2") (pinfunction "2_2") (pintype "bidirectional"))
      (node (ref "C6") (pin "2") (pinfunction "2_2") (pintype "bidirectional"))
      (node (ref "C7") (pin "2") (pinfunction "2_2") (pintype "bidirectional"))
      (node (ref "C8") (pin "2") (pinfunction "2_2") (pintype "bidirectional"))
      (node (ref "C9") (pin "2") (pinfunction "2_2") (pintype "bidirectional"))
      (node (ref "IC1") (pin "1") (pinfunction "VBAT_1") (pintype "power_in"))
      (node (ref "IC1") (pin "13") (pinfunction "VREF+_13") (pintype "power_in"))
      (node (ref "IC1") (pin "19") (pinfunction "VDD_1_19") (pintype "power_in"))
      (node (ref "IC1") (pin "32") (pinfunction "VDD_2_32") (pintype "power_in"))
      (node (ref "IC1") (pin "48") (pinfunction "VDD_3_48") (pintype "power_in"))
      (node (ref "IC1") (pin "64") (pinfunction "VDD_4_64") (pintype "power_in"))
      (node (ref "Q1") (pin "1") (pinfunction "G_1") (pintype "bidirectional"))
      (node (ref "Q2") (pin "1") (pinfunction "G_1") (pintype "bidirectional"))
      (node (ref "Q3") (pin "1") (pinfunction "G_1") (pintype "bidirectional"))
      (node (ref "Q5") (pin "1") (pinfunction "G_1") (pintype "bidirectional"))
      (node (ref "R101") (pin "1") (pinfunction "1_1") (pintype "passive"))
      (node (ref "R2") (pin "1") (pinfunction "1_1") (pintype "passive"))
      (node (ref "R23") (pin "1") (pinfunction "1_1") (pintype "passive"))
      (node (ref "R25") (pin "1") (pinfunction "1_1") (pintype "passive"))
      (node (ref "R27") (pin "1") (pinfunction "1_1") (pintype "passive"))
      (node (ref "R29") (pin "1") (pinfunction "1_1") (pintype "passive"))
      (node (ref "R31") (pin "2") (pinfunction "2_2") (pintype "passive"))
      (node (ref "R33") (pin "1") (pinfunction "1_1") (pintype "passive"))
      (node (ref "R35") (pin "1") (pinfunction "1_1") (pintype "passive"))
      (node (ref "R37") (pin "1") (pinfunction "1_1") (pintype "passive"))
      (node (ref "R39") (pin "1") (pinfunction "1_1") (pintype "passive"))
      (node (ref "R41") (pin "1") (pinfunction "1_1") (pintype "passive"))
      (node (ref "R43") (pin "1") (pinfunction "1_1") (pintype "passive"))
      (node (ref "R45") (pin "1") (pinfunction "1_1") (pintype "passive"))
      (node (ref "R51") (pin "1") (pinfunction "1_1") (pintype "passive"))
      (node (ref "R67") (pin "2") (pinfunction "2_2") (pintype "passive"))
      (node (ref "R69") (pin "2") (pinfunction "2_2") (pintype "passive"))
      (node (ref "R71") (pin "2") (pinfunction "2_2") (pintype "passive"))
      (node (ref "R73") (pin "2") (pinfunction "2_2") (pintype "passive"))
      (node (ref "R81") (pin "1") (pinfunction "1_1") (pintype "passive"))
      (node (ref "R85") (pin "1") (pinfunction "1_1") (pintype "passive"))
      (node (ref "R87") (pin "1") (pinfunction "1_1") (pintype "passive"))
      (node (ref "R89") (pin "1") (pinfunction "1_1") (pintype "passive"))
      (node (ref "R91") (pin "1") (pinfunction "1_1") (pintype "passive"))
      (node (ref "R95") (pin "1") (pinfunction "1_1") (pintype "passive"))
      (node (ref "R97") (pin "1") (pinfunction "1_1") (pintype "passive"))
      (node (ref "R99") (pin "1") (pinfunction "1_1") (pintype "passive"))
      (node (ref "S1") (pin "C1") (pinfunction "COM_1_C1") (pintype "bidirectional"))
      (node (ref "SL1") (pin "1") (pinfunction "1_1") (pintype "passive"))
      (node (ref "U1") (pin "2") (pinfunction "OUT_2") (pintype "output"))
      (node (ref "U1") (pin "4") (pinfunction "OUT_4") (pintype "output"))
      (node (ref "X22") (pin "2") (pinfunction "2_2") (pintype "passive"))
    )
    (net (code "2") (name "5V") (class "Default")
      (node (ref "C22") (pin "2") (pinfunction "2_2") (pintype "bidirectional"))
      (node (ref "IC2") (pin "3") (pinfunction "VCC_3") (pintype "bidirectional"))
      (node (ref "IC2") (pin "5") (pinfunction "EN_5") (pintype "bidirectional"))
      (node (ref "IC4") (pin "15") (pinfunction "VREF_15") (pintype "bidirectional"))
      (node (ref "IC4") (pin "16") (pinfunction "VDD_16") (pintype "bidirectional"))
      (node (ref "J1") (pin "1") (pinfunction "1_1") (pintype "bidirectional"))
      (node (ref "J1") (pin "5") (pinfunction "5_5") (pintype "bidirectional"))
      (node (ref "J2") (pin "1") (pinfunction "1_1") (pintype "bidirectional"))
      (node (ref "J2") (pin "5") (pinfunction "5_5") (pintype "bidirectional"))
      (node (ref "LED18-G") (pin "A") (pinfunction "A_A") (pintype "passive"))
      (node (ref "LED19-Y") (pin "A") (pinfunction "A_A") (pintype "passive"))
      (node (ref "LED3-R") (pin "A") (pinfunction "A_A") (pintype "passive"))
      (node (ref "LED5-G") (pin "A") (pinfunction "A_A") (pintype "passive"))
      (node (ref "LED6-Y") (pin "A") (pinfunction "A_A") (pintype "passive"))
      (node (ref "R100") (pin "1") (pinfunction "1_1") (pintype "passive"))
      (node (ref "R102") (pin "1") (pinfunction "1_1") (pintype "passive"))
      (node (ref "R14") (pin "1") (pinfunction "1_1") (pintype "passive"))
      (node (ref "R16") (pin "1") (pinfunction "1_1") (pintype "passive"))
      (node (ref "R18") (pin "1") (pinfunction "1_1") (pintype "passive"))
      (node (ref "R20") (pin "1") (pinfunction "1_1") (pintype "passive"))
      (node (ref "R22") (pin "1") (pinfunction "1_1") (pintype "passive"))
      (node (ref "R24") (pin "1") (pinfunction "1_1") (pintype "passive"))
      (node (ref "R26") (pin "1") (pinfunction "1_1") (pintype "passive"))
      (node (ref "R28") (pin "1") (pinfunction "1_1") (pintype "passive"))
      (node (ref "R30") (pin "1") (pinfunction "1_1") (pintype "passive"))
      (node (ref "R32") (pin "2") (pinfunction "2_2") (pintype "passive"))
      (node (ref "R34") (pin "1") (pinfunction "1_1") (pintype "passive"))
      (node (ref "R36") (pin "1") (pinfunction "1_1") (pintype "passive"))
      (node (ref "R38") (pin "1") (pinfunction "1_1") (pintype "passive"))
      (node (ref "R40") (pin "1") (pinfunction "1_1") (pintype "passive"))
      (node (ref "R42") (pin "1") (pinfunction "1_1") (pintype "passive"))
      (node (ref "R44") (pin "1") (pinfunction "1_1") (pintype "passive"))
      (node (ref "R46") (pin "1") (pinfunction "1_1") (pintype "passive"))
      (node (ref "R48") (pin "1") (pinfunction "1_1") (pintype "passive"))
      (node (ref "R50") (pin "1") (pinfunction "1_1") (pintype "passive"))
      (node (ref "R52") (pin "1") (pinfunction "1_1") (pintype "passive"))
      (node (ref "R54") (pin "1") (pinfunction "1_1") (pintype "passive"))
      (node (ref "R56") (pin "1") (pinfunction "1_1") (pintype "passive"))
      (node (ref "R58") (pin "1") (pinfunction "1_1") (pintype "passive"))
      (node (ref "R6") (pin "1") (pinfunction "1_1") (pintype "passive"))
      (node (ref "R60") (pin "1") (pinfunction "1_1") (pintype "passive"))
      (node (ref "R62") (pin "1") (pinfunction "1_1") (pintype "passive"))
      (node (ref "R64") (pin "1") (pinfunction "1_1") (pintype "passive"))
      (node (ref "R66") (pin "1") (pinfunction "1_1") (pintype "passive"))
      (node (ref "R68") (pin "2") (pinfunction "2_2") (pintype "passive"))
      (node (ref "R70") (pin "2") (pinfunction "2_2") (pintype "passive"))
      (node (ref "R72") (pin "2") (pinfunction "2_2") (pintype "passive"))
      (node (ref "R74") (pin "2") (pinfunction "2_2") (pintype "passive"))
      (node (ref "R8") (pin "1") (pinfunction "1_1") (pintype "passive"))
      (node (ref "R82") (pin "1") (pinfunction "1_1") (pintype "passive"))
      (node (ref "R86") (pin "1") (pinfunction "1_1") (pintype "passive"))
      (node (ref "R88") (pin "1") (pinfunction "1_1") (pintype "passive"))
      (node (ref "R90") (pin "1") (pinfunction "1_1") (pintype "passive"))
      (node (ref "R92") (pin "1") (pinfunction "1_1") (pintype "passive"))
      (node (ref "R96") (pin "1") (pinfunction "1_1") (pintype "passive"))
      (node (ref "R98") (pin "1") (pinfunction "1_1") (pintype "passive"))
      (node (ref "U1") (pin "3") (pinfunction "IN_3") (pintype "input"))
      (node (ref "X1") (pin "4") (pinfunction "4_4") (pintype "passive"))
      (node (ref "X2") (pin "4") (pinfunction "4_4") (pintype "passive"))
      (node (ref "X22") (pin "1") (pinfunction "1_1") (pintype "passive"))
      (node (ref "X3") (pin "4") (pinfunction "4_4") (pintype "passive"))
      (node (ref "X4") (pin "4") (pinfunction "4_4") (pintype "passive"))
      (node (ref "X5") (pin "4") (pinfunction "4_4") (pintype "passive"))
      (node (ref "X6") (pin "4") (pinfunction "4_4") (pintype "passive"))
    )
    (net (code "3") (name "ADC0") (class "Default")
      (node (ref "IC4") (pin "1") (pinfunction "CH0_1") (pintype "bidirectional"))
      (node (ref "X12") (pin "2") (pinfunction "2_2") (pintype "passive"))
    )
    (net (code "4") (name "ADC1") (class "Default")
      (node (ref "IC4") (pin "2") (pinfunction "CH1_2") (pintype "bidirectional"))
      (node (ref "X25") (pin "2") (pinfunction "2_2") (pintype "passive"))
    )
    (net (code "5") (name "ADC2") (class "Default")
      (node (ref "IC4") (pin "3") (pinfunction "CH2_3") (pintype "bidirectional"))
      (node (ref "X7") (pin "2") (pinfunction "2_2") (pintype "passive"))
    )
    (net (code "6") (name "ADC3") (class "Default")
      (node (ref "IC4") (pin "4") (pinfunction "CH3_4") (pintype "bidirectional"))
      (node (ref "X23") (pin "2") (pinfunction "2_2") (pintype "passive"))
    )
    (net (code "7") (name "ADC4") (class "Default")
      (node (ref "IC4") (pin "5") (pinfunction "CH4_5") (pintype "bidirectional"))
      (node (ref "X10") (pin "2") (pinfunction "2_2") (pintype "passive"))
    )
    (net (code "8") (name "ADC5") (class "Default")
      (node (ref "IC4") (pin "6") (pinfunction "CH5_6") (pintype "bidirectional"))
      (node (ref "X18") (pin "2") (pinfunction "2_2") (pintype "passive"))
    )
    (net (code "9") (name "ADC6") (class "Default")
      (node (ref "IC4") (pin "7") (pinfunction "CH6_7") (pintype "bidirectional"))
      (node (ref "X20") (pin "2") (pinfunction "2_2") (pintype "passive"))
    )
    (net (code "10") (name "ADC7") (class "Default")
      (node (ref "IC4") (pin "8") (pinfunction "CH7_8") (pintype "bidirectional"))
      (node (ref "X21") (pin "2") (pinfunction "2_2") (pintype "passive"))
    )
    (net (code "11") (name "CANH") (class "Default")
      (node (ref "IC2") (pin "7") (pinfunction "CANH_7") (pintype "bidirectional"))
      (node (ref "J1") (pin "2") (pinfunction "2_2") (pintype "bidirectional"))
      (node (ref "J1") (pin "6") (pinfunction "6_6") (pintype "bidirectional"))
      (node (ref "J2") (pin "2") (pinfunction "2_2") (pintype "bidirectional"))
      (node (ref "J2") (pin "6") (pinfunction "6_6") (pintype "bidirectional"))
      (node (ref "R5") (pin "2") (pinfunction "2_2") (pintype "passive"))
    )
    (net (code "12") (name "CANL") (class "Default")
      (node (ref "IC2") (pin "6") (pinfunction "CANL_6") (pintype "bidirectional"))
      (node (ref "J1") (pin "3") (pinfunction "3_3") (pintype "bidirectional"))
      (node (ref "J1") (pin "7") (pinfunction "7_7") (pintype "bidirectional"))
      (node (ref "J2") (pin "3") (pinfunction "3_3") (pintype "bidirectional"))
      (node (ref "J2") (pin "7") (pinfunction "7_7") (pintype "bidirectional"))
      (node (ref "R5") (pin "1") (pinfunction "1_1") (pintype "passive"))
    )
    (net (code "13") (name "CAN_RX") (class "Default")
      (node (ref "IC1") (pin "44") (pinfunction "PA11_44") (pintype "bidirectional"))
      (node (ref "IC2") (pin "4") (pinfunction "RXD_4") (pintype "bidirectional"))
      (node (ref "R78") (pin "2") (pinfunction "2_2") (pintype "passive"))
    )
    (net (code "14") (name "CAN_TX") (class "Default")
      (node (ref "IC1") (pin "45") (pinfunction "PA12_45") (pintype "bidirectional"))
      (node (ref "IC2") (pin "1") (pinfunction "TXD_1") (pintype "bidirectional"))
      (node (ref "R77") (pin "2") (pinfunction "2_2") (pintype "passive"))
    )
    (net (code "15") (name "ENCODER1-A") (class "Default")
      (node (ref "IC1") (pin "14") (pinfunction "PA0-WKUP_14") (pintype "bidirectional"))
      (node (ref "R47") (pin "1") (pinfunction "1_1") (pintype "passive"))
      (node (ref "X1") (pin "5") (pinfunction "5_5") (pintype "passive"))
    )
    (net (code "16") (name "ENCODER1-B") (class "Default")
      (node (ref "IC1") (pin "15") (pinfunction "PA1_15") (pintype "bidirectional"))
      (node (ref "R11") (pin "1") (pinfunction "1_1") (pintype "passive"))
      (node (ref "X1") (pin "3") (pinfunction "3_3") (pintype "passive"))
    )
    (net (code "17") (name "ENCODER2-A") (class "Default")
      (node (ref "IC1") (pin "37") (pinfunction "PC6_37") (pintype "bidirectional"))
      (node (ref "R49") (pin "1") (pinfunction "1_1") (pintype "passive"))
      (node (ref "X2") (pin "5") (pinfunction "5_5") (pintype "passive"))
    )
    (net (code "18") (name "ENCODER2-B") (class "Default")
      (node (ref "IC1") (pin "38") (pinfunction "PC7_38") (pintype "bidirectional"))
      (node (ref "R13") (pin "1") (pinfunction "1_1") (pintype "passive"))
      (node (ref "X2") (pin "3") (pinfunction "3_3") (pintype "passive"))
    )
    (net (code "19") (name "ENCODER3-A") (class "Default")
      (node (ref "IC1") (pin "41") (pinfunction "PA8_41") (pintype "bidirectional"))
      (node (ref "R53") (pin "1") (pinfunction "1_1") (pintype "passive"))
      (node (ref "X3") (pin "5") (pinfunction "5_5") (pintype "passive"))
    )
    (net (code "20") (name "ENCODER3-B") (class "Default")
      (node (ref "IC1") (pin "42") (pinfunction "PA9_42") (pintype "bidirectional"))
      (node (ref "R15") (pin "1") (pinfunction "1_1") (pintype "passive"))
      (node (ref "X3") (pin "3") (pinfunction "3_3") (pintype "passive"))
    )
    (net (code "21") (name "ENCODER4-A") (class "Default")
      (node (ref "IC1") (pin "50") (pinfunction "PA15_50") (pintype "bidirectional"))
      (node (ref "R4") (pin "1") (pinfunction "1_1") (pintype "passive"))
      (node (ref "X4") (pin "5") (pinfunction "5_5") (pintype "passive"))
    )
    (net (code "22") (name "ENCODER4-B") (class "Default")
      (node (ref "IC1") (pin "55") (pinfunction "PB3_55") (pintype "bidirectional"))
      (node (ref "R17") (pin "1") (pinfunction "1_1") (pintype "passive"))
      (node (ref "X4") (pin "3") (pinfunction "3_3") (pintype "passive"))
    )
    (net (code "23") (name "ENCODER5-A") (class "Default")
      (node (ref "IC1") (pin "56") (pinfunction "PB4_56") (pintype "bidirectional"))
      (node (ref "R7") (pin "1") (pinfunction "1_1") (pintype "passive"))
      (node (ref "X5") (pin "5") (pinfunction "5_5") (pintype "passive"))
    )
    (net (code "24") (name "ENCODER5-B") (class "Default")
      (node (ref "IC1") (pin "57") (pinfunction "PB5_57") (pintype "bidirectional"))
      (node (ref "R19") (pin "1") (pinfunction "1_1") (pintype "passive"))
      (node (ref "X5") (pin "3") (pinfunction "3_3") (pintype "passive"))
    )
    (net (code "25") (name "ENCODER6-A") (class "Default")
      (node (ref "IC1") (pin "58") (pinfunction "PB6_58") (pintype "bidirectional"))
      (node (ref "R9") (pin "1") (pinfunction "1_1") (pintype "passive"))
      (node (ref "X6") (pin "5") (pinfunction "5_5") (pintype "passive"))
    )
    (net (code "26") (name "ENCODER6-B") (class "Default")
      (node (ref "IC1") (pin "59") (pinfunction "PB7_59") (pintype "bidirectional"))
      (node (ref "R21") (pin "1") (pinfunction "1_1") (pintype "passive"))
      (node (ref "X6") (pin "3") (pinfunction "3_3") (pintype "passive"))
    )
    (net (code "27") (name "GND") (class "Default")
      (node (ref "C10") (pin "1") (pinfunction "1_1") (pintype "bidirectional"))
      (node (ref "C11") (pin "1") (pinfunction "1_1") (pintype "bidirectional"))
      (node (ref "C12") (pin "1") (pinfunction "1_1") (pintype "bidirectional"))
      (node (ref "C13") (pin "1") (pinfunction "1_1") (pintype "bidirectional"))
      (node (ref "C14") (pin "1") (pinfunction "1_1") (pintype "bidirectional"))
      (node (ref "C15") (pin "1") (pinfunction "1_1") (pintype "bidirectional"))
      (node (ref "C16") (pin "1") (pinfunction "1_1") (pintype "bidirectional"))
      (node (ref "C17") (pin "1") (pinfunction "1_1") (pintype "bidirectional"))
      (node (ref "C18") (pin "1") (pinfunction "1_1") (pintype "bidirectional"))
      (node (ref "C19") (pin "1") (pinfunction "1_1") (pintype "bidirectional"))
      (node (ref "C2") (pin "1") (pinfunction "1_1") (pintype "bidirectional"))
      (node (ref "C20") (pin "1") (pinfunction "1_1") (pintype "bidirectional"))
      (node (ref "C21") (pin "1") (pinfunction "1_1") (pintype "bidirectional"))
      (node (ref "C22") (pin "1") (pinfunction "1_1") (pintype "bidirectional"))
      (node (ref "C23") (pin "1") (pinfunction "1_1") (pintype "bidirectional"))
      (node (ref "C3") (pin "1") (pinfunction "1_1") (pintype "bidirectional"))
      (node (ref "C4") (pin "1") (pinfunction "1_1") (pintype "bidirectional"))
      (node (ref "C5") (pin "1") (pinfunction "1_1") (pintype "bidirectional"))
      (node (ref "C6") (pin "1") (pinfunction "1_1") (pintype "bidirectional"))
      (node (ref "C7") (pin "1") (pinfunction "1_1") (pintype "bidirectional"))
      (node (ref "C8") (pin "1") (pinfunction "1_1") (pintype "bidirectional"))
      (node (ref "C9") (pin "1") (pinfunction "1_1") (pintype "bidirectional"))
      (node (ref "IC1") (pin "12") (pinfunction "VSSA_12") (pintype "power_in"))
      (node (ref "IC1") (pin "18") (pinfunction "VSS_1_18") (pintype "power_in"))
      (node (ref "IC1") (pin "31") (pinfunction "VSS_2_31") (pintype "power_in"))
      (node (ref "IC1") (pin "47") (pinfunction "VSS_3_47") (pintype "power_in"))
      (node (ref "IC1") (pin "63") (pinfunction "VSS_4_63") (pintype "power_in"))
      (node (ref "IC2") (pin "2") (pinfunction "GND_2") (pintype "bidirectional"))
      (node (ref "IC2") (pin "8") (pinfunction "S_8") (pintype "bidirectional"))
      (node (ref "IC4") (pin "14") (pinfunction "AGND_14") (pintype "bidirectional"))
      (node (ref "IC4") (pin "9") (pinfunction "DGND_9") (pintype "bidirectional"))
      (node (ref "J1") (pin "4") (pinfunction "4_4") (pintype "bidirectional"))
      (node (ref "J1") (pin "8") (pinfunction "8_8") (pintype "bidirectional"))
      (node (ref "J2") (pin "4") (pinfunction "4_4") (pintype "bidirectional"))
      (node (ref "J2") (pin "8") (pinfunction "8_8") (pintype "bidirectional"))
      (node (ref "LED2-R") (pin "K") (pinfunction "K_K") (pintype "passive"))
      (node (ref "Q10") (pin "2") (pinfunction "S_2") (pintype "bidirectional"))
      (node (ref "Q9") (pin "2") (pinfunction "S_2") (pintype "bidirectional"))
      (node (ref "R1") (pin "2") (pinfunction "2_2") (pintype "passive"))
      (node (ref "R3") (pin "2") (pinfunction "2_2") (pintype "passive"))
      (node (ref "S2") (pin "C1") (pinfunction "COM_1_C1") (pintype "bidirectional"))
      (node (ref "S2") (pin "D1") (pinfunction "COM_2_D1") (pintype "bidirectional"))
      (node (ref "SL1") (pin "3") (pinfunction "3_3") (pintype "passive"))
      (node (ref "TR1") (pin "2") (pinfunction "S_2") (pintype "bidirectional"))
      (node (ref "TR10") (pin "2") (pinfunction "S_2") (pintype "bidirectional"))
      (node (ref "TR11") (pin "2") (pinfunction "S_2") (pintype "bidirectional"))
      (node (ref "TR12") (pin "2") (pinfunction "S_2") (pintype "bidirectional"))
      (node (ref "TR13") (pin "2") (pinfunction "S_2") (pintype "bidirectional"))
      (node (ref "TR14") (pin "2") (pinfunction "S_2") (pintype "bidirectional"))
      (node (ref "TR15") (pin "2") (pinfunction "S_2") (pintype "bidirectional"))
      (node (ref "TR16") (pin "2") (pinfunction "S_2") (pintype "bidirectional"))
      (node (ref "TR17") (pin "2") (pinfunction "S_2") (pintype "bidirectional"))
      (node (ref "TR2") (pin "2") (pinfunction "S_2") (pintype "bidirectional"))
      (node (ref "TR21") (pin "2") (pinfunction "S_2") (pintype "bidirectional"))
      (node (ref "TR3") (pin "2") (pinfunction "S_2") (pintype "bidirectional"))
      (node (ref "TR4") (pin "2") (pinfunction "S_2") (pintype "bidirectional"))
      (node (ref "TR5") (pin "2") (pinfunction "S_2") (pintype "bidirectional"))
      (node (ref "TR6") (pin "2") (pinfunction "S_2") (pintype "bidirectional"))
      (node (ref "TR7") (pin "2") (pinfunction "S_2") (pintype "bidirectional"))
      (node (ref "TR8") (pin "2") (pinfunction "S_2") (pintype "bidirectional"))
      (node (ref "TR9") (pin "2") (pinfunction "S_2") (pintype "bidirectional"))
      (node (ref "U1") (pin "1") (pinfunction "GND_1") (pintype "passive"))
      (node (ref "X1") (pin "1") (pinfunction "1_1") (pintype "passive"))
      (node (ref "X10") (pin "3") (pinfunction "3_3") (pintype "passive"))
      (node (ref "X12") (pin "3") (pinfunction "3_3") (pintype "passive"))
      (node (ref "X14") (pin "4") (pinfunction "4_4") (pintype "passive"))
      (node (ref "X17") (pin "4") (pinfunction "4_4") (pintype "passive"))
      (node (ref "X18") (pin "3") (pinfunction "3_3") (pintype "passive"))
      (node (ref "X2") (pin "1") (pinfunction "1_1") (pintype "passive"))
      (node (ref "X20") (pin "3") (pinfunction "3_3") (pintype "passive"))
      (node (ref "X21") (pin "3") (pinfunction "3_3") (pintype "passive"))
      (node (ref "X22") (pin "3") (pinfunction "3_3") (pintype "passive"))
      (node (ref "X23") (pin "3") (pinfunction "3_3") (pintype "passive"))
      (node (ref "X24") (pin "3") (pinfunction "3_3") (pintype "passive"))
      (node (ref "X25") (pin "3") (pinfunction "3_3") (pintype "passive"))
      (node (ref "X27") (pin "3") (pinfunction "3_3") (pintype "passive"))
      (node (ref "X28") (pin "3") (pinfunction "3_3") (pintype "passive"))
      (node (ref "X29") (pin "3") (pinfunction "3_3") (pintype "passive"))
      (node (ref "X3") (pin "1") (pinfunction "1_1") (pintype "passive"))
      (node (ref "X30") (pin "3") (pinfunction "3_3") (pintype "passive"))
      (node (ref "X32") (pin "3") (pinfunction "3_3") (pintype "passive"))
      (node (ref "X33") (pin "3") (pinfunction "3_3") (pintype "passive"))
      (node (ref "X34") (pin "3") (pinfunction "3_3") (pintype "passive"))
      (node (ref "X35") (pin "3") (pinfunction "3_3") (pintype "passive"))
      (node (ref "X4") (pin "1") (pinfunction "1_1") (pintype "passive"))
      (node (ref "X5") (pin "1") (pinfunction "1_1") (pintype "passive"))
      (node (ref "X6") (pin "1") (pinfunction "1_1") (pintype "passive"))
      (node (ref "X7") (pin "3") (pinfunction "3_3") (pintype "passive"))
      (node (ref "X9") (pin "4") (pinfunction "4_4") (pintype "passive"))
    )
    (net (code "28") (name "MISO_5V") (class "Default")
      (node (ref "IC4") (pin "12") (pinfunction "DOUT_12") (pintype "bidirectional"))
      (node (ref "Q3") (pin "3") (pinfunction "D_3") (pintype "bidirectional"))
      (node (ref "R28") (pin "2") (pinfunction "2_2") (pintype "passive"))
    )
    (net (code "29") (name "MOSI_5V") (class "Default")
      (node (ref "IC4") (pin "11") (pinfunction "DIN_11") (pintype "bidirectional"))
      (node (ref "Q2") (pin "3") (pinfunction "D_3") (pintype "bidirectional"))
      (node (ref "R26") (pin "2") (pinfunction "2_2") (pintype "passive"))
    )
    (net (code "30") (name "NRST") (class "Default")
      (node (ref "C23") (pin "2") (pinfunction "2_2") (pintype "bidirectional"))
      (node (ref "IC1") (pin "7") (pinfunction "NRST_7") (pintype "bidirectional"))
      (node (ref "S2") (pin "A1") (pinfunction "NO_1_A1") (pintype "bidirectional"))
      (node (ref "SL1") (pin "5") (pinfunction "5_5") (pintype "passive"))
    )
    (net (code "31") (name "NSS_5V") (class "Default")
      (node (ref "IC4") (pin "10") (pinfunction "~{CS}/SHDN_10") (pintype "bidirectional"))
      (node (ref "Q1") (pin "3") (pinfunction "D_3") (pintype "bidirectional"))
      (node (ref "R24") (pin "2") (pinfunction "2_2") (pintype "passive"))
    )
    (net (code "32") (name "Net-(IC1-BOOT0)") (class "Default")
      (node (ref "IC1") (pin "60") (pinfunction "BOOT0_60") (pintype "bidirectional"))
      (node (ref "R1") (pin "1") (pinfunction "1_1") (pintype "passive"))
    )
    (net (code "33") (name "Net-(LED1-G-PadA)") (class "Default")
      (node (ref "LED1-G") (pin "A") (pinfunction "A_A") (pintype "passive"))
      (node (ref "R6") (pin "2") (pinfunction "2_2") (pintype "passive"))
    )
    (net (code "34") (name "Net-(LED2-R-PadA)") (class "Default")
      (node (ref "LED2-R") (pin "A") (pinfunction "A_A") (pintype "passive"))
      (node (ref "R2") (pin "2") (pinfunction "2_2") (pintype "passive"))
    )
    (net (code "35") (name "Net-(LED3-R-PadK)") (class "Default")
      (node (ref "LED3-R") (pin "K") (pinfunction "K_K") (pintype "passive"))
      (node (ref "R3") (pin "1") (pinfunction "1_1") (pintype "passive"))
    )
    (net (code "36") (name "Net-(LED4-G-PadA)") (class "Default")
      (node (ref "LED4-G") (pin "A") (pinfunction "A_A") (pintype "passive"))
      (node (ref "R8") (pin "2") (pinfunction "2_2") (pintype "passive"))
    )
    (net (code "37") (name "Net-(LED5-G-PadK)") (class "Default")
      (node (ref "LED5-G") (pin "K") (pinfunction "K_K") (pintype "passive"))
      (node (ref "R10") (pin "1") (pinfunction "1_1") (pintype "passive"))
    )
    (net (code "38") (name "Net-(LED6-Y-PadK)") (class "Default")
      (node (ref "LED6-Y") (pin "K") (pinfunction "K_K") (pintype "passive"))
      (node (ref "R12") (pin "1") (pinfunction "1_1") (pintype "passive"))
    )
    (net (code "39") (name "Net-(LED7-Y-PadA)") (class "Default")
      (node (ref "LED7-Y") (pin "A") (pinfunction "A_A") (pintype "passive"))
      (node (ref "R14") (pin "2") (pinfunction "2_2") (pintype "passive"))
    )
    (net (code "40") (name "Net-(LED8-Y-PadA)") (class "Default")
      (node (ref "LED8-Y") (pin "A") (pinfunction "A_A") (pintype "passive"))
      (node (ref "R16") (pin "2") (pinfunction "2_2") (pintype "passive"))
    )
    (net (code "41") (name "Net-(LED9-Y-PadA)") (class "Default")
      (node (ref "LED9-Y") (pin "A") (pinfunction "A_A") (pintype "passive"))
      (node (ref "R18") (pin "2") (pinfunction "2_2") (pintype "passive"))
    )
    (net (code "42") (name "Net-(LED10-Y-PadA)") (class "Default")
      (node (ref "LED10-Y") (pin "A") (pinfunction "A_A") (pintype "passive"))
      (node (ref "R20") (pin "2") (pinfunction "2_2") (pintype "passive"))
    )
    (net (code "43") (name "Net-(LED11-Y-PadA)") (class "Default")
      (node (ref "LED11-Y") (pin "A") (pinfunction "A_A") (pintype "passive"))
      (node (ref "R22") (pin "2") (pinfunction "2_2") (pintype "passive"))
    )
    (net (code "44") (name "Net-(LED12-G-PadA)") (class "Default")
      (node (ref "LED12-G") (pin "A") (pinfunction "A_A") (pintype "passive"))
      (node (ref "R56") (pin "2") (pinfunction "2_2") (pintype "passive"))
    )
    (net (code "45") (name "Net-(LED13-Y-PadA)") (class "Default")
      (node (ref "LED13-Y") (pin "A") (pinfunction "A_A") (pintype "passive"))
      (node (ref "R58") (pin "2") (pinfunction "2_2") (pintype "passive"))
    )
    (net (code "46") (name "Net-(LED14-B-PadA)") (class "Default")
      (node (ref "LED14-B") (pin "A") (pinfunction "A_A") (pintype "passive"))
      (node (ref "R60") (pin "2") (pinfunction "2_2") (pintype "passive"))
    )
    (net (code "47") (name "Net-(LED15-B-PadA)") (class "Default")
      (node (ref "LED15-B") (pin "A") (pinfunction "A_A") (pintype "passive"))
      (node (ref "R62") (pin "2") (pinfunction "2_2") (pintype "passive"))
    )
    (net (code "48") (name "Net-(LED16-B-PadA)") (class "Default")
      (node (ref "LED16-B") (pin "A") (pinfunction "A_A") (pintype "passive"))
      (node (ref "R64") (pin "2") (pinfunction "2_2") (pintype "passive"))
    )
    (net (code "49") (name "Net-(LED17-B-PadA)") (class "Default")
      (node (ref "LED17-B") (pin "A") (pinfunction "A_A") (pintype "passive"))
      (node (ref "R66") (pin "2") (pinfunction "2_2") (pintype "passive"))
    )
    (net (code "50") (name "Net-(LED18-G-PadK)") (class "Default")
      (node (ref "LED18-G") (pin "K") (pinfunction "K_K") (pintype "passive"))
      (node (ref "R75") (pin "1") (pinfunction "1_1") (pintype "passive"))
    )
    (net (code "51") (name "Net-(LED19-Y-PadK)") (class "Default")
      (node (ref "LED19-Y") (pin "K") (pinfunction "K_K") (pintype "passive"))
      (node (ref "R76") (pin "1") (pinfunction "1_1") (pintype "passive"))
    )
    (net (code "52") (name "Net-(LED20-G-PadA)") (class "Default")
      (node (ref "LED20-G") (pin "A") (pinfunction "A_A") (pintype "passive"))
      (node (ref "R48") (pin "2") (pinfunction "2_2") (pintype "passive"))
    )
    (net (code "53") (name "Net-(LED21-G-PadA)") (class "Default")
      (node (ref "LED21-G") (pin "A") (pinfunction "A_A") (pintype "passive"))
      (node (ref "R50") (pin "2") (pinfunction "2_2") (pintype "passive"))
    )
    (net (code "54") (name "Net-(LED23-G-PadA)") (class "Default")
      (node (ref "LED23-G") (pin "A") (pinfunction "A_A") (pintype "passive"))
      (node (ref "R54") (pin "2") (pinfunction "2_2") (pintype "passive"))
    )
    (net (code "55") (name "Net-(Q9-D)") (class "Default")
      (node (ref "Q9") (pin "3") (pinfunction "D_3") (pintype "bidirectional"))
      (node (ref "R75") (pin "2") (pinfunction "2_2") (pintype "passive"))
    )
    (net (code "56") (name "Net-(Q9-G)") (class "Default")
      (node (ref "Q9") (pin "1") (pinfunction "G_1") (pintype "bidirectional"))
      (node (ref "R77") (pin "1") (pinfunction "1_1") (pintype "passive"))
    )
    (net (code "57") (name "Net-(Q10-D)") (class "Default")
      (node (ref "Q10") (pin "3") (pinfunction "D_3") (pintype "bidirectional"))
      (node (ref "R76") (pin "2") (pinfunction "2_2") (pintype "passive"))
    )
    (net (code "58") (name "Net-(Q10-G)") (class "Default")
      (node (ref "Q10") (pin "1") (pinfunction "G_1") (pintype "bidirectional"))
      (node (ref "R78") (pin "1") (pinfunction "1_1") (pintype "passive"))
    )
    (net (code "59") (name "Net-(R31-Pad1)") (class "Default")
      (node (ref "R31") (pin "1") (pinfunction "1_1") (pintype "passive"))
      (node (ref "R32") (pin "1") (pinfunction "1_1") (pintype "passive"))
      (node (ref "X9") (pin "1") (pinfunction "1_1") (pintype "passive"))
    )
    (net (code "60") (name "Net-(R33-Pad2)") (class "Default")
      (node (ref "R33") (pin "2") (pinfunction "2_2") (pintype "passive"))
      (node (ref "R34") (pin "2") (pinfunction "2_2") (pintype "passive"))
      (node (ref "X25") (pin "1") (pinfunction "1_1") (pintype "passive"))
    )
    (net (code "61") (name "Net-(R35-Pad2)") (class "Default")
      (node (ref "R35") (pin "2") (pinfunction "2_2") (pintype "passive"))
      (node (ref "R36") (pin "2") (pinfunction "2_2") (pintype "passive"))
      (node (ref "X12") (pin "1") (pinfunction "1_1") (pintype "passive"))
    )
    (net (code "62") (name "Net-(R37-Pad2)") (class "Default")
      (node (ref "R37") (pin "2") (pinfunction "2_2") (pintype "passive"))
      (node (ref "R38") (pin "2") (pinfunction "2_2") (pintype "passive"))
      (node (ref "X7") (pin "1") (pinfunction "1_1") (pintype "passive"))
    )
    (net (code "63") (name "Net-(R39-Pad2)") (class "Default")
      (node (ref "R39") (pin "2") (pinfunction "2_2") (pintype "passive"))
      (node (ref "R40") (pin "2") (pinfunction "2_2") (pintype "passive"))
      (node (ref "X23") (pin "1") (pinfunction "1_1") (pintype "passive"))
    )
    (net (code "64") (name "Net-(R41-Pad2)") (class "Default")
      (node (ref "R41") (pin "2") (pinfunction "2_2") (pintype "passive"))
      (node (ref "R42") (pin "2") (pinfunction "2_2") (pintype "passive"))
      (node (ref "X10") (pin "1") (pinfunction "1_1") (pintype "passive"))
    )
    (net (code "65") (name "Net-(R43-Pad2)") (class "Default")
      (node (ref "R43") (pin "2") (pinfunction "2_2") (pintype "passive"))
      (node (ref "R44") (pin "2") (pinfunction "2_2") (pintype "passive"))
      (node (ref "X18") (pin "1") (pinfunction "1_1") (pintype "passive"))
    )
    (net (code "66") (name "Net-(R45-Pad2)") (class "Default")
      (node (ref "R45") (pin "2") (pinfunction "2_2") (pintype "passive"))
      (node (ref "R46") (pin "2") (pinfunction "2_2") (pintype "passive"))
      (node (ref "X20") (pin "1") (pinfunction "1_1") (pintype "passive"))
    )
    (net (code "67") (name "Net-(R51-Pad2)") (class "Default")
      (node (ref "R51") (pin "2") (pinfunction "2_2") (pintype "passive"))
      (node (ref "R52") (pin "2") (pinfunction "2_2") (pintype "passive"))
      (node (ref "X21") (pin "1") (pinfunction "1_1") (pintype "passive"))
    )
    (net (code "68") (name "Net-(R67-Pad1)") (class "Default")
      (node (ref "R67") (pin "1") (pinfunction "1_1") (pintype "passive"))
      (node (ref "R68") (pin "1") (pinfunction "1_1") (pintype "passive"))
      (node (ref "X17") (pin "1") (pinfunction "1_1") (pintype "passive"))
    )
    (net (code "69") (name "Net-(R69-Pad1)") (class "Default")
      (node (ref "R69") (pin "1") (pinfunction "1_1") (pintype "passive"))
      (node (ref "R70") (pin "1") (pinfunction "1_1") (pintype "passive"))
      (node (ref "X14") (pin "1") (pinfunction "1_1") (pintype "passive"))
    )
    (net (code "70") (name "Net-(R71-Pad1)") (class "Default")
      (node (ref "R71") (pin "1") (pinfunction "1_1") (pintype "passive"))
      (node (ref "R72") (pin "1") (pinfunction "1_1") (pintype "passive"))
      (node (ref "X13") (pin "1") (pinfunction "1_1") (pintype "passive"))
    )
    (net (code "71") (name "Net-(R73-Pad1)") (class "Default")
      (node (ref "R73") (pin "1") (pinfunction "1_1") (pintype "passive"))
      (node (ref "R74") (pin "1") (pinfunction "1_1") (pintype "passive"))
      (node (ref "X11") (pin "1") (pinfunction "1_1") (pintype "passive"))
    )
    (net (code "72") (name "Net-(R81-Pad2)") (class "Default")
      (node (ref "R81") (pin "2") (pinfunction "2_2") (pintype "passive"))
      (node (ref "R82") (pin "2") (pinfunction "2_2") (pintype "passive"))
      (node (ref "X24") (pin "1") (pinfunction "1_1") (pintype "passive"))
    )
    (net (code "73") (name "Net-(R85-Pad2)") (class "Default")
      (node (ref "R85") (pin "2") (pinfunction "2_2") (pintype "passive"))
      (node (ref "R86") (pin "2") (pinfunction "2_2") (pintype "passive"))
      (node (ref "X27") (pin "1") (pinfunction "1_1") (pintype "passive"))
    )
    (net (code "74") (name "Net-(R87-Pad2)") (class "Default")
      (node (ref "R87") (pin "2") (pinfunction "2_2") (pintype "passive"))
      (node (ref "R88") (pin "2") (pinfunction "2_2") (pintype "passive"))
      (node (ref "X28") (pin "1") (pinfunction "1_1") (pintype "passive"))
    )
    (net (code "75") (name "Net-(R89-Pad2)") (class "Default")
      (node (ref "R89") (pin "2") (pinfunction "2_2") (pintype "passive"))
      (node (ref "R90") (pin "2") (pinfunction "2_2") (pintype "passive"))
      (node (ref "X29") (pin "1") (pinfunction "1_1") (pintype "passive"))
    )
    (net (code "76") (name "Net-(R91-Pad2)") (class "Default")
      (node (ref "R91") (pin "2") (pinfunction "2_2") (pintype "passive"))
      (node (ref "R92") (pin "2") (pinfunction "2_2") (pintype "passive"))
      (node (ref "X30") (pin "1") (pinfunction "1_1") (pintype "passive"))
    )
    (net (code "77") (name "Net-(R95-Pad2)") (class "Default")
      (node (ref "R95") (pin "2") (pinfunction "2_2") (pintype "passive"))
      (node (ref "R96") (pin "2") (pinfunction "2_2") (pintype "passive"))
      (node (ref "X32") (pin "1") (pinfunction "1_1") (pintype "passive"))
    )
    (net (code "78") (name "Net-(R97-Pad2)") (class "Default")
      (node (ref "R97") (pin "2") (pinfunction "2_2") (pintype "passive"))
      (node (ref "R98") (pin "2") (pinfunction "2_2") (pintype "passive"))
      (node (ref "X33") (pin "1") (pinfunction "1_1") (pintype "passive"))
    )
    (net (code "79") (name "Net-(R100-Pad2)") (class "Default")
      (node (ref "R100") (pin "2") (pinfunction "2_2") (pintype "passive"))
      (node (ref "R99") (pin "2") (pinfunction "2_2") (pintype "passive"))
      (node (ref "X34") (pin "1") (pinfunction "1_1") (pintype "passive"))
    )
    (net (code "80") (name "Net-(R101-Pad2)") (class "Default")
      (node (ref "R101") (pin "2") (pinfunction "2_2") (pintype "passive"))
      (node (ref "R102") (pin "2") (pinfunction "2_2") (pintype "passive"))
      (node (ref "X35") (pin "1") (pinfunction "1_1") (pintype "passive"))
    )
    (net (code "81") (name "Net-(TR1-D)") (class "Default")
      (node (ref "LED1-G") (pin "K") (pinfunction "K_K") (pintype "passive"))
      (node (ref "TR1") (pin "3") (pinfunction "D_3") (pintype "bidirectional"))
    )
    (net (code "82") (name "Net-(TR1-G)") (class "Default")
      (node (ref "R4") (pin "2") (pinfunction "2_2") (pintype "passive"))
      (node (ref "TR1") (pin "1") (pinfunction "G_1") (pintype "bidirectional"))
    )
    (net (code "83") (name "Net-(TR2-D)") (class "Default")
      (node (ref "LED4-G") (pin "K") (pinfunction "K_K") (pintype "passive"))
      (node (ref "TR2") (pin "3") (pinfunction "D_3") (pintype "bidirectional"))
    )
    (net (code "84") (name "Net-(TR2-G)") (class "Default")
      (node (ref "R7") (pin "2") (pinfunction "2_2") (pintype "passive"))
      (node (ref "TR2") (pin "1") (pinfunction "G_1") (pintype "bidirectional"))
    )
    (net (code "85") (name "Net-(TR3-D)") (class "Default")
      (node (ref "R10") (pin "2") (pinfunction "2_2") (pintype "passive"))
      (node (ref "TR3") (pin "3") (pinfunction "D_3") (pintype "bidirectional"))
    )
    (net (code "86") (name "Net-(TR3-G)") (class "Default")
      (node (ref "R9") (pin "2") (pinfunction "2_2") (pintype "passive"))
      (node (ref "TR3") (pin "1") (pinfunction "G_1") (pintype "bidirectional"))
    )
    (net (code "87") (name "Net-(TR4-D)") (class "Default")
      (node (ref "R12") (pin "2") (pinfunction "2_2") (pintype "passive"))
      (node (ref "TR4") (pin "3") (pinfunction "D_3") (pintype "bidirectional"))
    )
    (net (code "88") (name "Net-(TR4-G)") (class "Default")
      (node (ref "R11") (pin "2") (pinfunction "2_2") (pintype "passive"))
      (node (ref "TR4") (pin "1") (pinfunction "G_1") (pintype "bidirectional"))
    )
    (net (code "89") (name "Net-(TR5-D)") (class "Default")
      (node (ref "LED7-Y") (pin "K") (pinfunction "K_K") (pintype "passive"))
      (node (ref "TR5") (pin "3") (pinfunction "D_3") (pintype "bidirectional"))
    )
    (net (code "90") (name "Net-(TR5-G)") (class "Default")
      (node (ref "R13") (pin "2") (pinfunction "2_2") (pintype "passive"))
      (node (ref "TR5") (pin "1") (pinfunction "G_1") (pintype "bidirectional"))
    )
    (net (code "91") (name "Net-(TR6-D)") (class "Default")
      (node (ref "LED8-Y") (pin "K") (pinfunction "K_K") (pintype "passive"))
      (node (ref "TR6") (pin "3") (pinfunction "D_3") (pintype "bidirectional"))
    )
    (net (code "92") (name "Net-(TR6-G)") (class "Default")
      (node (ref "R15") (pin "2") (pinfunction "2_2") (pintype "passive"))
      (node (ref "TR6") (pin "1") (pinfunction "G_1") (pintype "bidirectional"))
    )
    (net (code "93") (name "Net-(TR7-D)") (class "Default")
      (node (ref "LED9-Y") (pin "K") (pinfunction "K_K") (pintype "passive"))
      (node (ref "TR7") (pin "3") (pinfunction "D_3") (pintype "bidirectional"))
    )
    (net (code "94") (name "Net-(TR7-G)") (class "Default")
      (node (ref "R17") (pin "2") (pinfunction "2_2") (pintype "passive"))
      (node (ref "TR7") (pin "1") (pinfunction "G_1") (pintype "bidirectional"))
    )
    (net (code "95") (name "Net-(TR8-D)") (class "Default")
      (node (ref "LED10-Y") (pin "K") (pinfunction "K_K") (pintype "passive"))
      (node (ref "TR8") (pin "3") (pinfunction "D_3") (pintype "bidirectional"))
    )
    (net (code "96") (name "Net-(TR8-G)") (class "Default")
      (node (ref "R19") (pin "2") (pinfunction "2_2") (pintype "passive"))
      (node (ref "TR8") (pin "1") (pinfunction "G_1") (pintype "bidirectional"))
    )
    (net (code "97") (name "Net-(TR9-D)") (class "Default")
      (node (ref "LED11-Y") (pin "K") (pinfunction "K_K") (pintype "passive"))
      (node (ref "TR9") (pin "3") (pinfunction "D_3") (pintype "bidirectional"))
    )
    (net (code "98") (name "Net-(TR9-G)") (class "Default")
      (node (ref "R21") (pin "2") (pinfunction "2_2") (pintype "passive"))
      (node (ref "TR9") (pin "1") (pinfunction "G_1") (pintype "bidirectional"))
    )
    (net (code "99") (name "Net-(TR10-D)") (class "Default")
      (node (ref "LED12-G") (pin "K") (pinfunction "K_K") (pintype "passive"))
      (node (ref "TR10") (pin "3") (pinfunction "D_3") (pintype "bidirectional"))
    )
    (net (code "100") (name "Net-(TR10-G)") (class "Default")
      (node (ref "R55") (pin "2") (pinfunction "2_2") (pintype "passive"))
      (node (ref "TR10") (pin "1") (pinfunction "G_1") (pintype "bidirectional"))
    )
    (net (code "101") (name "Net-(TR11-D)") (class "Default")
      (node (ref "LED13-Y") (pin "K") (pinfunction "K_K") (pintype "passive"))
      (node (ref "TR11") (pin "3") (pinfunction "D_3") (pintype "bidirectional"))
    )
    (net (code "102") (name "Net-(TR11-G)") (class "Default")
      (node (ref "R57") (pin "2") (pinfunction "2_2") (pintype "passive"))
      (node (ref "TR11") (pin "1") (pinfunction "G_1") (pintype "bidirectional"))
    )
    (net (code "103") (name "Net-(TR12-D)") (class "Default")
      (node (ref "LED14-B") (pin "K") (pinfunction "K_K") (pintype "passive"))
      (node (ref "TR12") (pin "3") (pinfunction "D_3") (pintype "bidirectional"))
    )
    (net (code "104") (name "Net-(TR12-G)") (class "Default")
      (node (ref "R59") (pin "2") (pinfunction "2_2") (pintype "passive"))
      (node (ref "TR12") (pin "1") (pinfunction "G_1") (pintype "bidirectional"))
    )
    (net (code "105") (name "Net-(TR13-D)") (class "Default")
      (node (ref "LED15-B") (pin "K") (pinfunction "K_K") (pintype "passive"))
      (node (ref "TR13") (pin "3") (pinfunction "D_3") (pintype "bidirectional"))
    )
    (net (code "106") (name "Net-(TR13-G)") (class "Default")
      (node (ref "R61") (pin "2") (pinfunction "2_2") (pintype "passive"))
      (node (ref "TR13") (pin "1") (pinfunction "G_1") (pintype "bidirectional"))
    )
    (net (code "107") (name "Net-(TR14-D)") (class "Default")
      (node (ref "LED16-B") (pin "K") (pinfunction "K_K") (pintype "passive"))
      (node (ref "TR14") (pin "3") (pinfunction "D_3") (pintype "bidirectional"))
    )
    (net (code "108") (name "Net-(TR14-G)") (class "Default")
      (node (ref "R63") (pin "2") (pinfunction "2_2") (pintype "passive"))
      (node (ref "TR14") (pin "1") (pinfunction "G_1") (pintype "bidirectional"))
    )
    (net (code "109") (name "Net-(TR15-D)") (class "Default")
      (node (ref "LED20-G") (pin "K") (pinfunction "K_K") (pintype "passive"))
      (node (ref "TR15") (pin "3") (pinfunction "D_3") (pintype "bidirectional"))
    )
    (net (code "110") (name "Net-(TR15-G)") (class "Default")
      (node (ref "R47") (pin "2") (pinfunction "2_2") (pintype "passive"))
      (node (ref "TR15") (pin "1") (pinfunction "G_1") (pintype "bidirectional"))
    )
    (net (code "111") (name "Net-(TR16-D)") (class "Default")
      (node (ref "LED21-G") (pin "K") (pinfunction "K_K") (pintype "passive"))
      (node (ref "TR16") (pin "3") (pinfunction "D_3") (pintype "bidirectional"))
    )
    (net (code "112") (name "Net-(TR16-G)") (class "Default")
      (node (ref "R49") (pin "2") (pinfunction "2_2") (pintype "passive"))
      (node (ref "TR16") (pin "1") (pinfunction "G_1") (pintype "bidirectional"))
    )
    (net (code "113") (name "Net-(TR17-D)") (class "Default")
      (node (ref "LED17-B") (pin "K") (pinfunction "K_K") (pintype "passive"))
      (node (ref "TR17") (pin "3") (pinfunction "D_3") (pintype "bidirectional"))
    )
    (net (code "114") (name "Net-(TR17-G)") (class "Default")
      (node (ref "R65") (pin "2") (pinfunction "2_2") (pintype "passive"))
      (node (ref "TR17") (pin "1") (pinfunction "G_1") (pintype "bidirectional"))
    )
    (net (code "115") (name "Net-(TR21-D)") (class "Default")
      (node (ref "LED23-G") (pin "K") (pinfunction "K_K") (pintype "passive"))
      (node (ref "TR21") (pin "3") (pinfunction "D_3") (pintype "bidirectional"))
    )
    (net (code "116") (name "Net-(TR21-G)") (class "Default")
      (node (ref "R53") (pin "2") (pinfunction "2_2") (pintype "passive"))
      (node (ref "TR21") (pin "1") (pinfunction "G_1") (pintype "bidirectional"))
    )
    (net (code "117") (name "PA10") (class "Default")
      (node (ref "IC1") (pin "43") (pinfunction "PA10_43") (pintype "bidirectional"))
      (node (ref "R59") (pin "1") (pinfunction "1_1") (pintype "passive"))
    )
    (net (code "118") (name "PB0") (class "Default")
      (node (ref "IC1") (pin "25") (pinfunction "PB0_25") (pintype "bidirectional"))
      (node (ref "X29") (pin "2") (pinfunction "2_2") (pintype "passive"))
    )
    (net (code "119") (name "PB1") (class "Default")
      (node (ref "IC1") (pin "26") (pinfunction "PB1_26") (pintype "bidirectional"))
      (node (ref "X30") (pin "2") (pinfunction "2_2") (pintype "passive"))
    )
    (net (code "120") (name "PB2") (class "Default")
      (node (ref "IC1") (pin "27") (pinfunction "PB2_27") (pintype "bidirectional"))
      (node (ref "R65") (pin "1") (pinfunction "1_1") (pintype "passive"))
    )
    (net (code "121") (name "PC1") (class "Default")
      (node (ref "IC1") (pin "9") (pinfunction "PC1_9") (pintype "bidirectional"))
      (node (ref "X24") (pin "2") (pinfunction "2_2") (pintype "passive"))
    )
    (net (code "122") (name "PC2") (class "Default")
      (node (ref "IC1") (pin "10") (pinfunction "PC2_10") (pintype "bidirectional"))
      (node (ref "X27") (pin "2") (pinfunction "2_2") (pintype "passive"))
    )
    (net (code "123") (name "PC4") (class "Default")
      (node (ref "IC1") (pin "24") (pinfunction "PC4_24") (pintype "bidirectional"))
      (node (ref "X28") (pin "2") (pinfunction "2_2") (pintype "passive"))
    )
    (net (code "124") (name "PC8") (class "Default")
      (node (ref "IC1") (pin "39") (pinfunction "PC8_39") (pintype "bidirectional"))
      (node (ref "R63") (pin "1") (pinfunction "1_1") (pintype "passive"))
    )
    (net (code "125") (name "PC9") (class "Default")
      (node (ref "IC1") (pin "40") (pinfunction "PC9_40") (pintype "bidirectional"))
      (node (ref "R61") (pin "1") (pinfunction "1_1") (pintype "passive"))
    )
    (net (code "126") (name "PC13") (class "Default")
      (node (ref "IC1") (pin "2") (pinfunction "PC13_2") (pintype "bidirectional"))
      (node (ref "X34") (pin "2") (pinfunction "2_2") (pintype "passive"))
    )
    (net (code "127") (name "PC14") (class "Default")
      (node (ref "IC1") (pin "3") (pinfunction "PC14-OSC32_IN_3") (pintype "bidirectional"))
      (node (ref "X35") (pin "2") (pinfunction "2_2") (pintype "passive"))
    )
    (net (code "128") (name "PC15") (class "Default")
      (node (ref "IC1") (pin "4") (pinfunction "PC15-OSC32_OUT_4") (pintype "bidirectional"))
      (node (ref "S1") (pin "A1") (pinfunction "NO_1_A1") (pintype "bidirectional"))
    )
    (net (code "129") (name "PH0") (class "Default")
      (node (ref "IC1") (pin "5") (pinfunction "PH0-OSC_IN_5") (pintype "bidirectional"))
      (node (ref "X32") (pin "2") (pinfunction "2_2") (pintype "passive"))
    )
    (net (code "130") (name "PH1") (class "Default")
      (node (ref "IC1") (pin "6") (pinfunction "PH1-OSC_OUT_6") (pintype "bidirectional"))
      (node (ref "X33") (pin "2") (pinfunction "2_2") (pintype "passive"))
    )
    (net (code "131") (name "SCK_5V") (class "Default")
      (node (ref "IC4") (pin "13") (pinfunction "CLK_13") (pintype "bidirectional"))
      (node (ref "Q5") (pin "3") (pinfunction "D_3") (pintype "bidirectional"))
      (node (ref "R30") (pin "2") (pinfunction "2_2") (pintype "passive"))
    )
    (net (code "132") (name "SCL1") (class "Default")
      (node (ref "IC1") (pin "61") (pinfunction "PB8_61") (pintype "bidirectional"))
      (node (ref "X14") (pin "3") (pinfunction "3_3") (pintype "passive"))
    )
    (net (code "133") (name "SCL2") (class "Default")
      (node (ref "IC1") (pin "28") (pinfunction "PB10_28") (pintype "bidirectional"))
      (node (ref "X17") (pin "3") (pinfunction "3_3") (pintype "passive"))
    )
    (net (code "134") (name "SDA1") (class "Default")
      (node (ref "IC1") (pin "62") (pinfunction "PB9_62") (pintype "bidirectional"))
      (node (ref "X14") (pin "2") (pinfunction "2_2") (pintype "passive"))
    )
    (net (code "135") (name "SDA2") (class "Default")
      (node (ref "IC1") (pin "29") (pinfunction "PB11_29") (pintype "bidirectional"))
      (node (ref "X17") (pin "2") (pinfunction "2_2") (pintype "passive"))
    )
    (net (code "136") (name "SPI1_MISO") (class "Default")
      (node (ref "IC1") (pin "22") (pinfunction "PA6_22") (pintype "bidirectional"))
      (node (ref "Q3") (pin "2") (pinfunction "S_2") (pintype "bidirectional"))
      (node (ref "R27") (pin "2") (pinfunction "2_2") (pintype "passive"))
    )
    (net (code "137") (name "SPI1_MOSI") (class "Default")
      (node (ref "IC1") (pin "23") (pinfunction "PA7_23") (pintype "bidirectional"))
      (node (ref "Q2") (pin "2") (pinfunction "S_2") (pintype "bidirectional"))
      (node (ref "R25") (pin "2") (pinfunction "2_2") (pintype "passive"))
    )
    (net (code "138") (name "SPI1_NSS") (class "Default")
      (node (ref "IC1") (pin "20") (pinfunction "PA4_20") (pintype "bidirectional"))
      (node (ref "Q1") (pin "2") (pinfunction "S_2") (pintype "bidirectional"))
      (node (ref "R23") (pin "2") (pinfunction "2_2") (pintype "passive"))
    )
    (net (code "139") (name "SPI1_SCK") (class "Default")
      (node (ref "IC1") (pin "21") (pinfunction "PA5_21") (pintype "bidirectional"))
      (node (ref "Q5") (pin "2") (pinfunction "S_2") (pintype "bidirectional"))
      (node (ref "R29") (pin "2") (pinfunction "2_2") (pintype "passive"))
    )
    (net (code "140") (name "SPI2_MISO") (class "Default")
      (node (ref "IC1") (pin "35") (pinfunction "PB14_35") (pintype "bidirectional"))
      (node (ref "X8") (pin "2") (pinfunction "2_2") (pintype "passive"))
    )
    (net (code "141") (name "SPI2_MOSI") (class "Default")
      (node (ref "IC1") (pin "36") (pinfunction "PB15_36") (pintype "bidirectional"))
      (node (ref "X8") (pin "1") (pinfunction "1_1") (pintype "passive"))
    )
    (net (code "142") (name "SPI2_NSS") (class "Default")
      (node (ref "IC1") (pin "33") (pinfunction "PB12_33") (pintype "bidirectional"))
      (node (ref "X8") (pin "4") (pinfunction "4_4") (pintype "passive"))
    )
    (net (code "143") (name "SPI2_SCK") (class "Default")
      (node (ref "IC1") (pin "34") (pinfunction "PB13_34") (pintype "bidirectional"))
      (node (ref "X8") (pin "3") (pinfunction "3_3") (pintype "passive"))
    )
    (net (code "144") (name "SWCLK") (class "Default")
      (node (ref "IC1") (pin "49") (pinfunction "PA14_49") (pintype "bidirectional"))
      (node (ref "SL1") (pin "2") (pinfunction "2_2") (pintype "passive"))
    )
    (net (code "145") (name "SWDIO") (class "Default")
      (node (ref "IC1") (pin "46") (pinfunction "PA13_46") (pintype "bidirectional"))
      (node (ref "SL1") (pin "4") (pinfunction "4_4") (pintype "passive"))
    )
    (net (code "146") (name "SWO") (class "Default")
      (node (ref "SL1") (pin "6") (pinfunction "6_6") (pintype "passive"))
    )
    (net (code "147") (name "UART_RX") (class "Default")
      (node (ref "IC1") (pin "54") (pinfunction "PD2_54") (pintype "bidirectional"))
      (node (ref "X11") (pin "3") (pinfunction "3_3") (pintype "passive"))
    )
    (net (code "148") (name "UART_TX") (class "Default")
      (node (ref "IC1") (pin "53") (pinfunction "PC12_53") (pintype "bidirectional"))
      (node (ref "X11") (pin "2") (pinfunction "2_2") (pintype "passive"))
    )
    (net (code "149") (name "USART1_RX") (class "Default")
      (node (ref "IC1") (pin "17") (pinfunction "PA3_17") (pintype "bidirectional"))
      (node (ref "R57") (pin "1") (pinfunction "1_1") (pintype "passive"))
      (node (ref "X9") (pin "3") (pinfunction "3_3") (pintype "passive"))
    )
    (net (code "150") (name "USART1_TX") (class "Default")
      (node (ref "IC1") (pin "16") (pinfunction "PA2_16") (pintype "bidirectional"))
      (node (ref "R55") (pin "1") (pinfunction "1_1") (pintype "passive"))
      (node (ref "X9") (pin "2") (pinfunction "2_2") (pintype "passive"))
    )
    (net (code "151") (name "USART2_RX") (class "Default")
      (node (ref "IC1") (pin "52") (pinfunction "PC11_52") (pintype "bidirectional"))
      (node (ref "X13") (pin "3") (pinfunction "3_3") (pintype "passive"))
    )
    (net (code "152") (name "USART2_TX") (class "Default")
      (node (ref "IC1") (pin "51") (pinfunction "PC10_51") (pintype "bidirectional"))
      (node (ref "X13") (pin "2") (pinfunction "2_2") (pintype "passive"))
    )
    (net (code "153") (name "VCAP") (class "Default")
      (node (ref "C20") (pin "2") (pinfunction "2_2") (pintype "bidirectional"))
      (node (ref "C21") (pin "2") (pinfunction "2_2") (pintype "bidirectional"))
      (node (ref "IC1") (pin "30") (pinfunction "VCAP_1_30") (pintype "power_in"))
    )
    (net (code "154") (name "unconnected-(IC1-PC0-Pad8)") (class "Default")
      (node (ref "IC1") (pin "8") (pinfunction "PC0_8") (pintype "bidirectional"))
    )
    (net (code "155") (name "unconnected-(IC1-PC3-Pad11)") (class "Default")
      (node (ref "IC1") (pin "11") (pinfunction "PC3_11") (pintype "bidirectional"))
    )
    (net (code "156") (name "unconnected-(J1-PadMH1)") (class "Default")
      (node (ref "J1") (pin "MH1") (pinfunction "MH1_MH1") (pintype "bidirectional"))
    )
    (net (code "157") (name "unconnected-(J1-PadMH2)") (class "Default")
      (node (ref "J1") (pin "MH2") (pinfunction "MH2_MH2") (pintype "bidirectional"))
    )
    (net (code "158") (name "unconnected-(J1-PadMH3)") (class "Default")
      (node (ref "J1") (pin "MH3") (pinfunction "MH3_MH3") (pintype "bidirectional"))
    )
    (net (code "159") (name "unconnected-(J1-PadMH4)") (class "Default")
      (node (ref "J1") (pin "MH4") (pinfunction "MH4_MH4") (pintype "bidirectional"))
    )
    (net (code "160") (name "unconnected-(J2-PadMH1)") (class "Default")
      (node (ref "J2") (pin "MH1") (pinfunction "MH1_MH1") (pintype "bidirectional"))
    )
    (net (code "161") (name "unconnected-(J2-PadMH2)") (class "Default")
      (node (ref "J2") (pin "MH2") (pinfunction "MH2_MH2") (pintype "bidirectional"))
    )
    (net (code "162") (name "unconnected-(J2-PadMH3)") (class "Default")
      (node (ref "J2") (pin "MH3") (pinfunction "MH3_MH3") (pintype "bidirectional"))
    )
    (net (code "163") (name "unconnected-(J2-PadMH4)") (class "Default")
      (node (ref "J2") (pin "MH4") (pinfunction "MH4_MH4") (pintype "bidirectional"))
    )
    (net (code "164") (name "unconnected-(S1-COM_2-PadD1)") (class "Default")
      (node (ref "S1") (pin "D1") (pinfunction "COM_2_D1") (pintype "bidirectional"))
    )
    (net (code "165") (name "unconnected-(S1-NO_2-PadB1)") (class "Default")
      (node (ref "S1") (pin "B1") (pinfunction "NO_2_B1") (pintype "bidirectional"))
    )
    (net (code "166") (name "unconnected-(S2-NO_2-PadB1)") (class "Default")
      (node (ref "S2") (pin "B1") (pinfunction "NO_2_B1") (pintype "bidirectional"))
    )
    (net (code "167") (name "unconnected-(X1-Pad2)") (class "Default")
      (node (ref "X1") (pin "2") (pinfunction "2_2") (pintype "passive"))
    )
    (net (code "168") (name "unconnected-(X2-Pad2)") (class "Default")
      (node (ref "X2") (pin "2") (pinfunction "2_2") (pintype "passive"))
    )
    (net (code "169") (name "unconnected-(X3-Pad2)") (class "Default")
      (node (ref "X3") (pin "2") (pinfunction "2_2") (pintype "passive"))
    )
    (net (code "170") (name "unconnected-(X4-Pad2)") (class "Default")
      (node (ref "X4") (pin "2") (pinfunction "2_2") (pintype "passive"))
    )
    (net (code "171") (name "unconnected-(X5-Pad2)") (class "Default")
      (node (ref "X5") (pin "2") (pinfunction "2_2") (pintype "passive"))
    )
    (net (code "172") (name "unconnected-(X6-Pad2)") (class "Default")
      (node (ref "X6") (pin "2") (pinfunction "2_2") (pintype "passive"))
    )
  )
)
